# GMSL_DESERIALIZER.net
KiCad netlist of a schematic drawn in Altium Designer
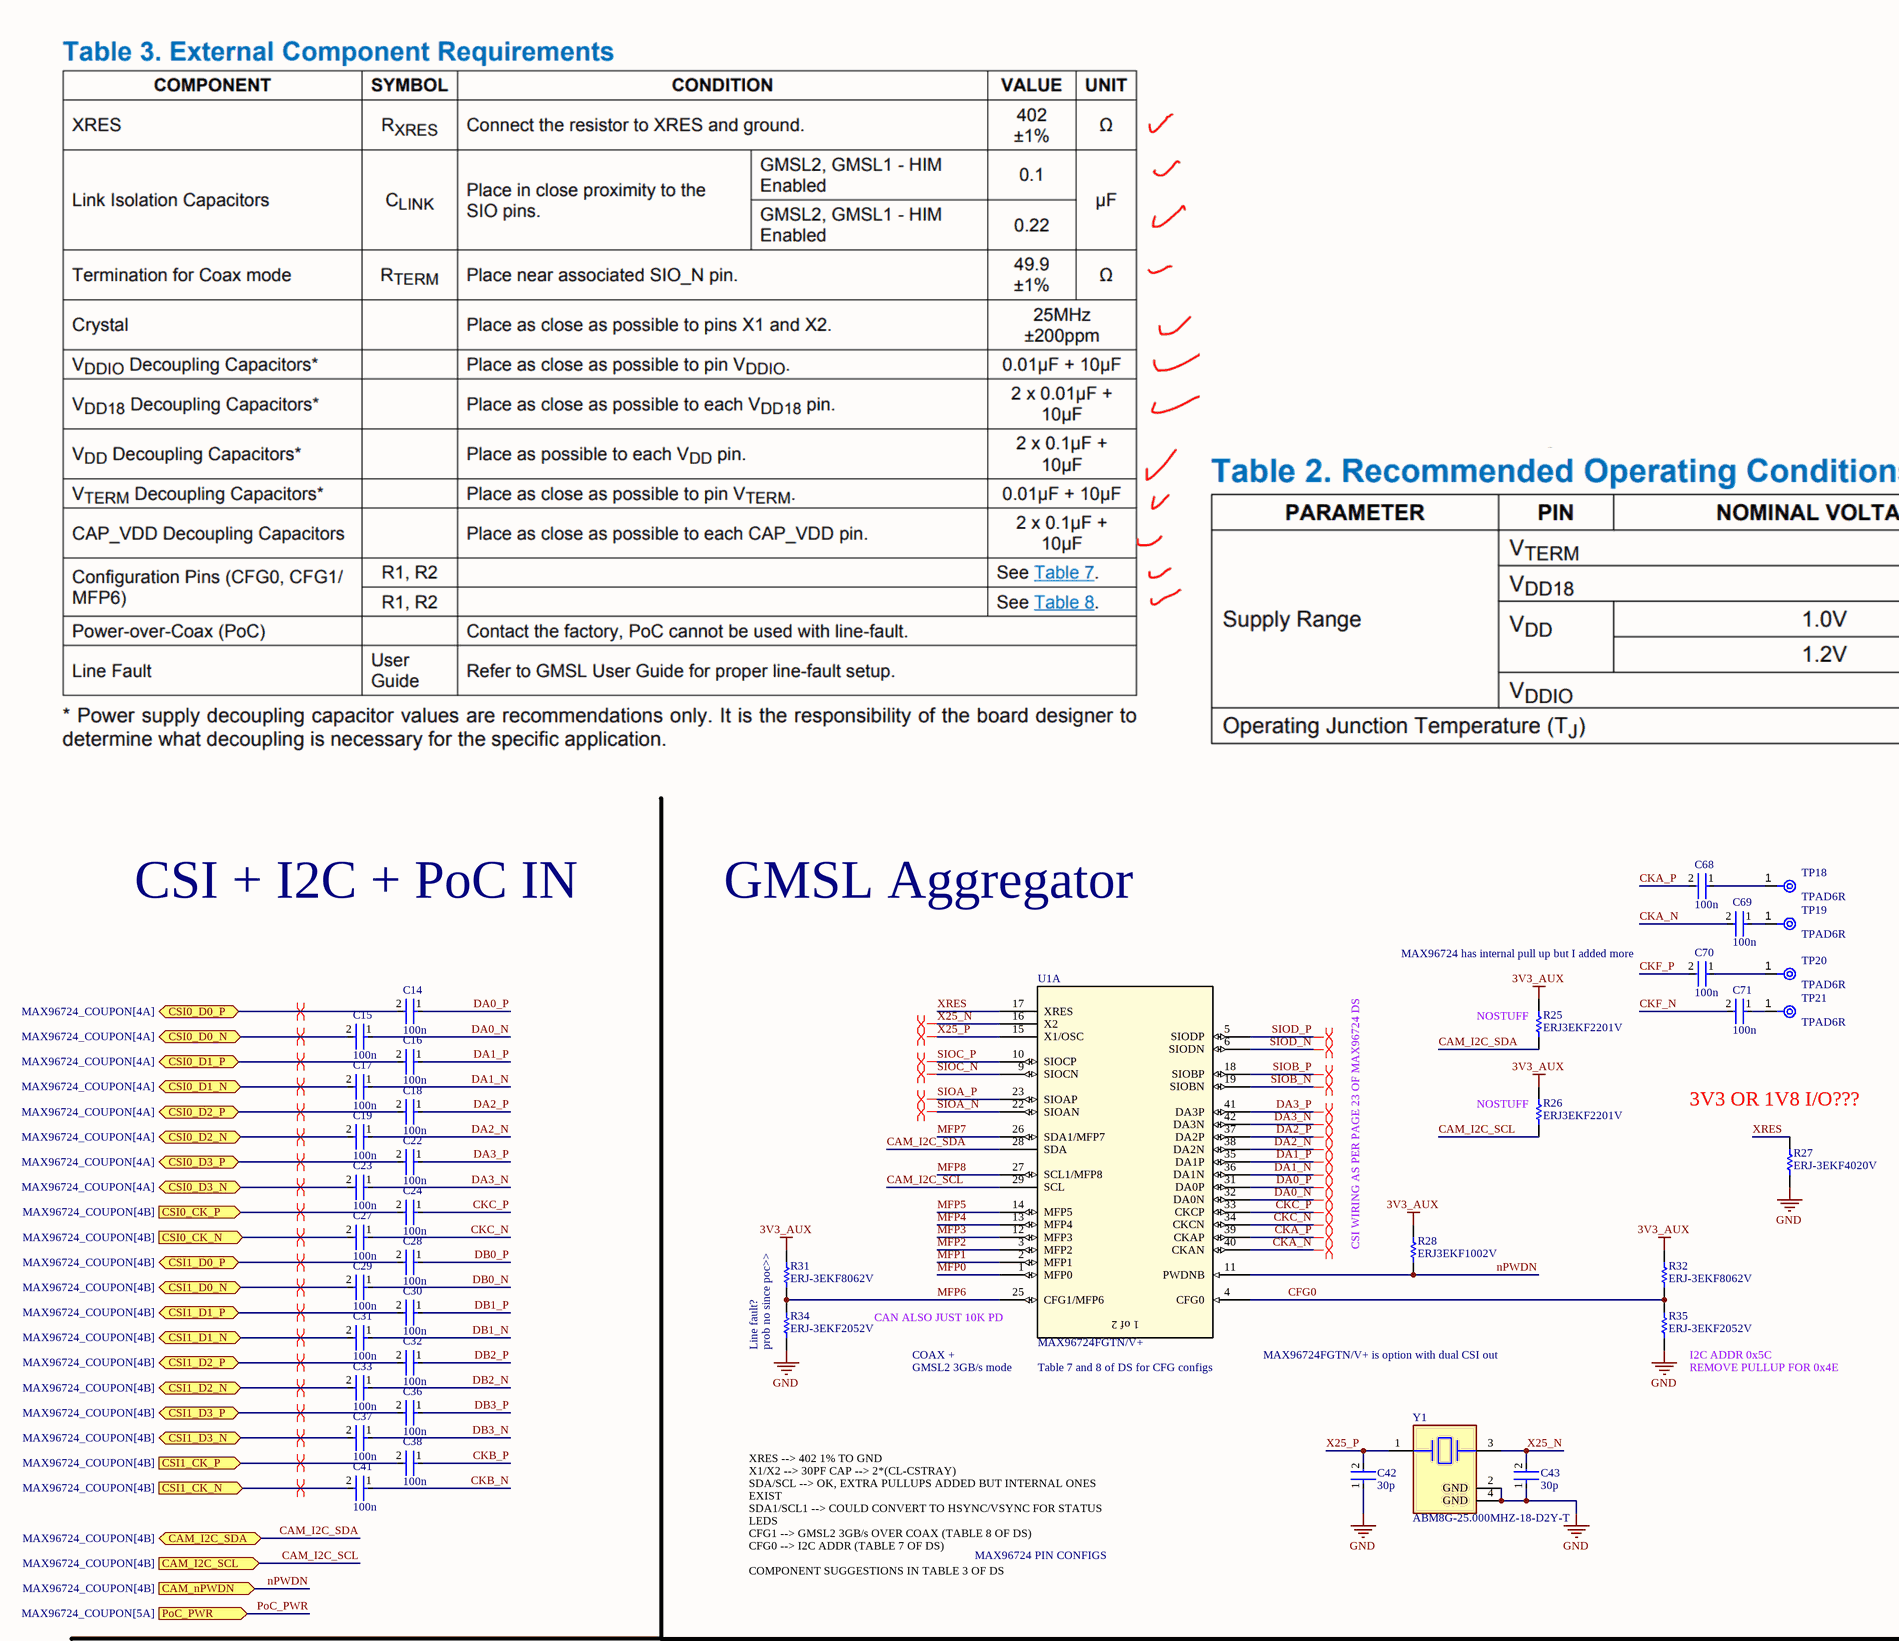
[diagram p0: GMSL_DESERIALIZER.SchDoc, top left]
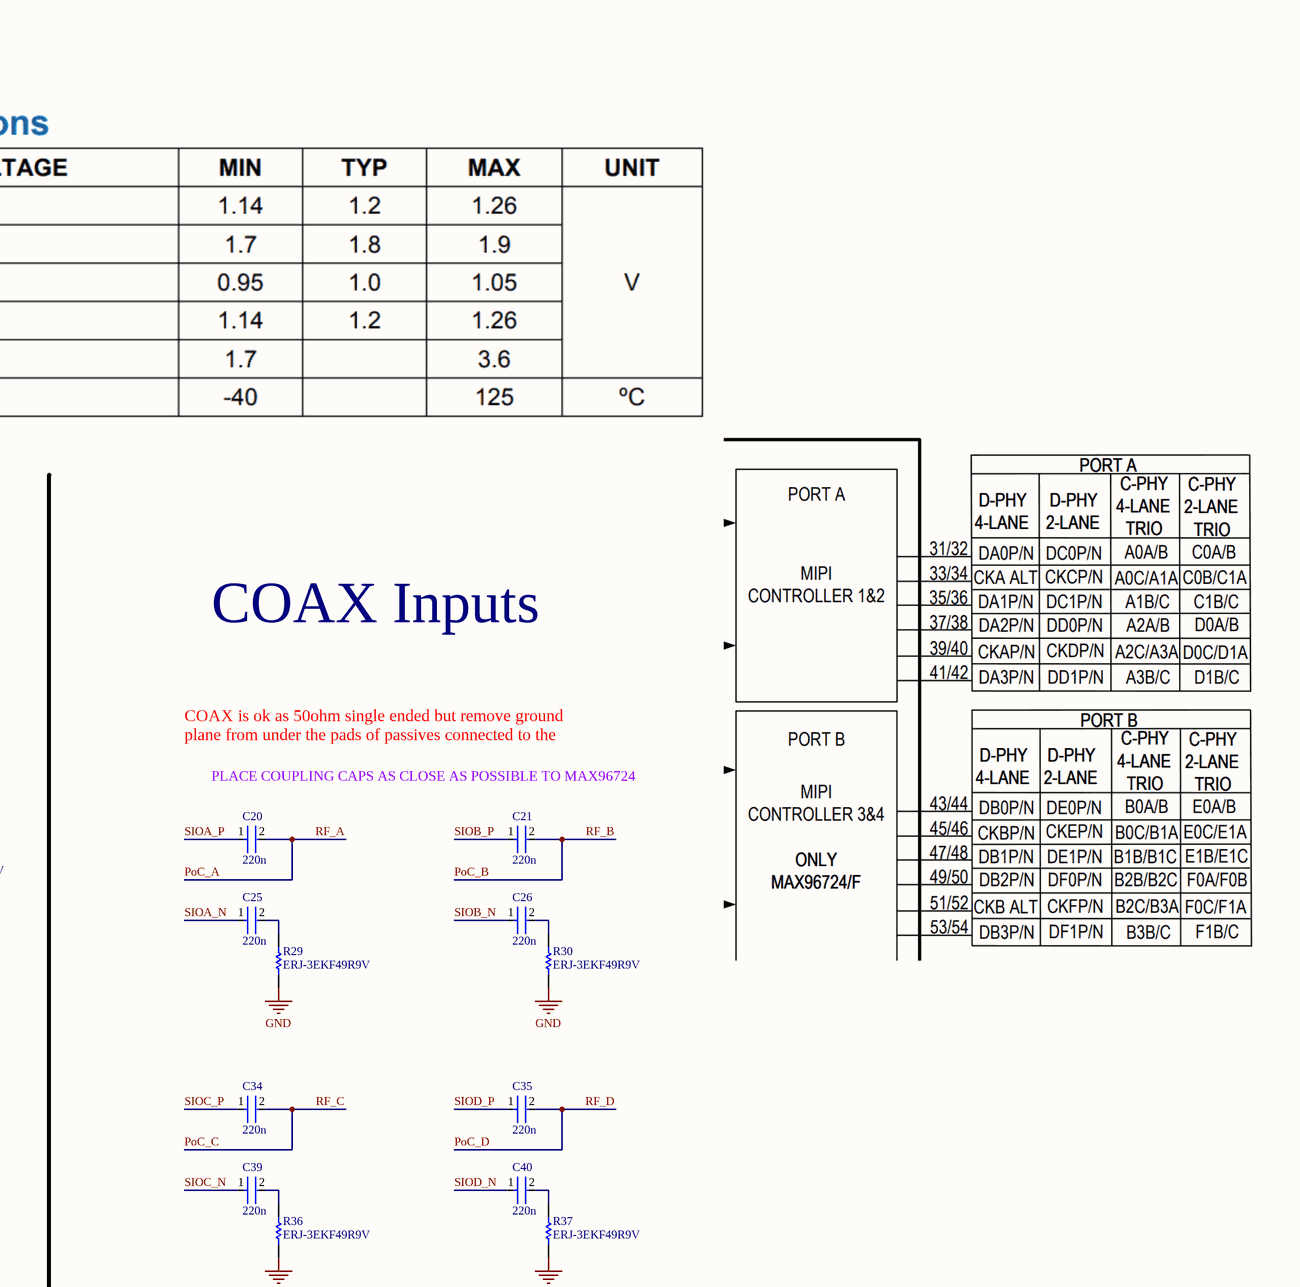
[diagram p1: GMSL_DESERIALIZER.SchDoc, top right]
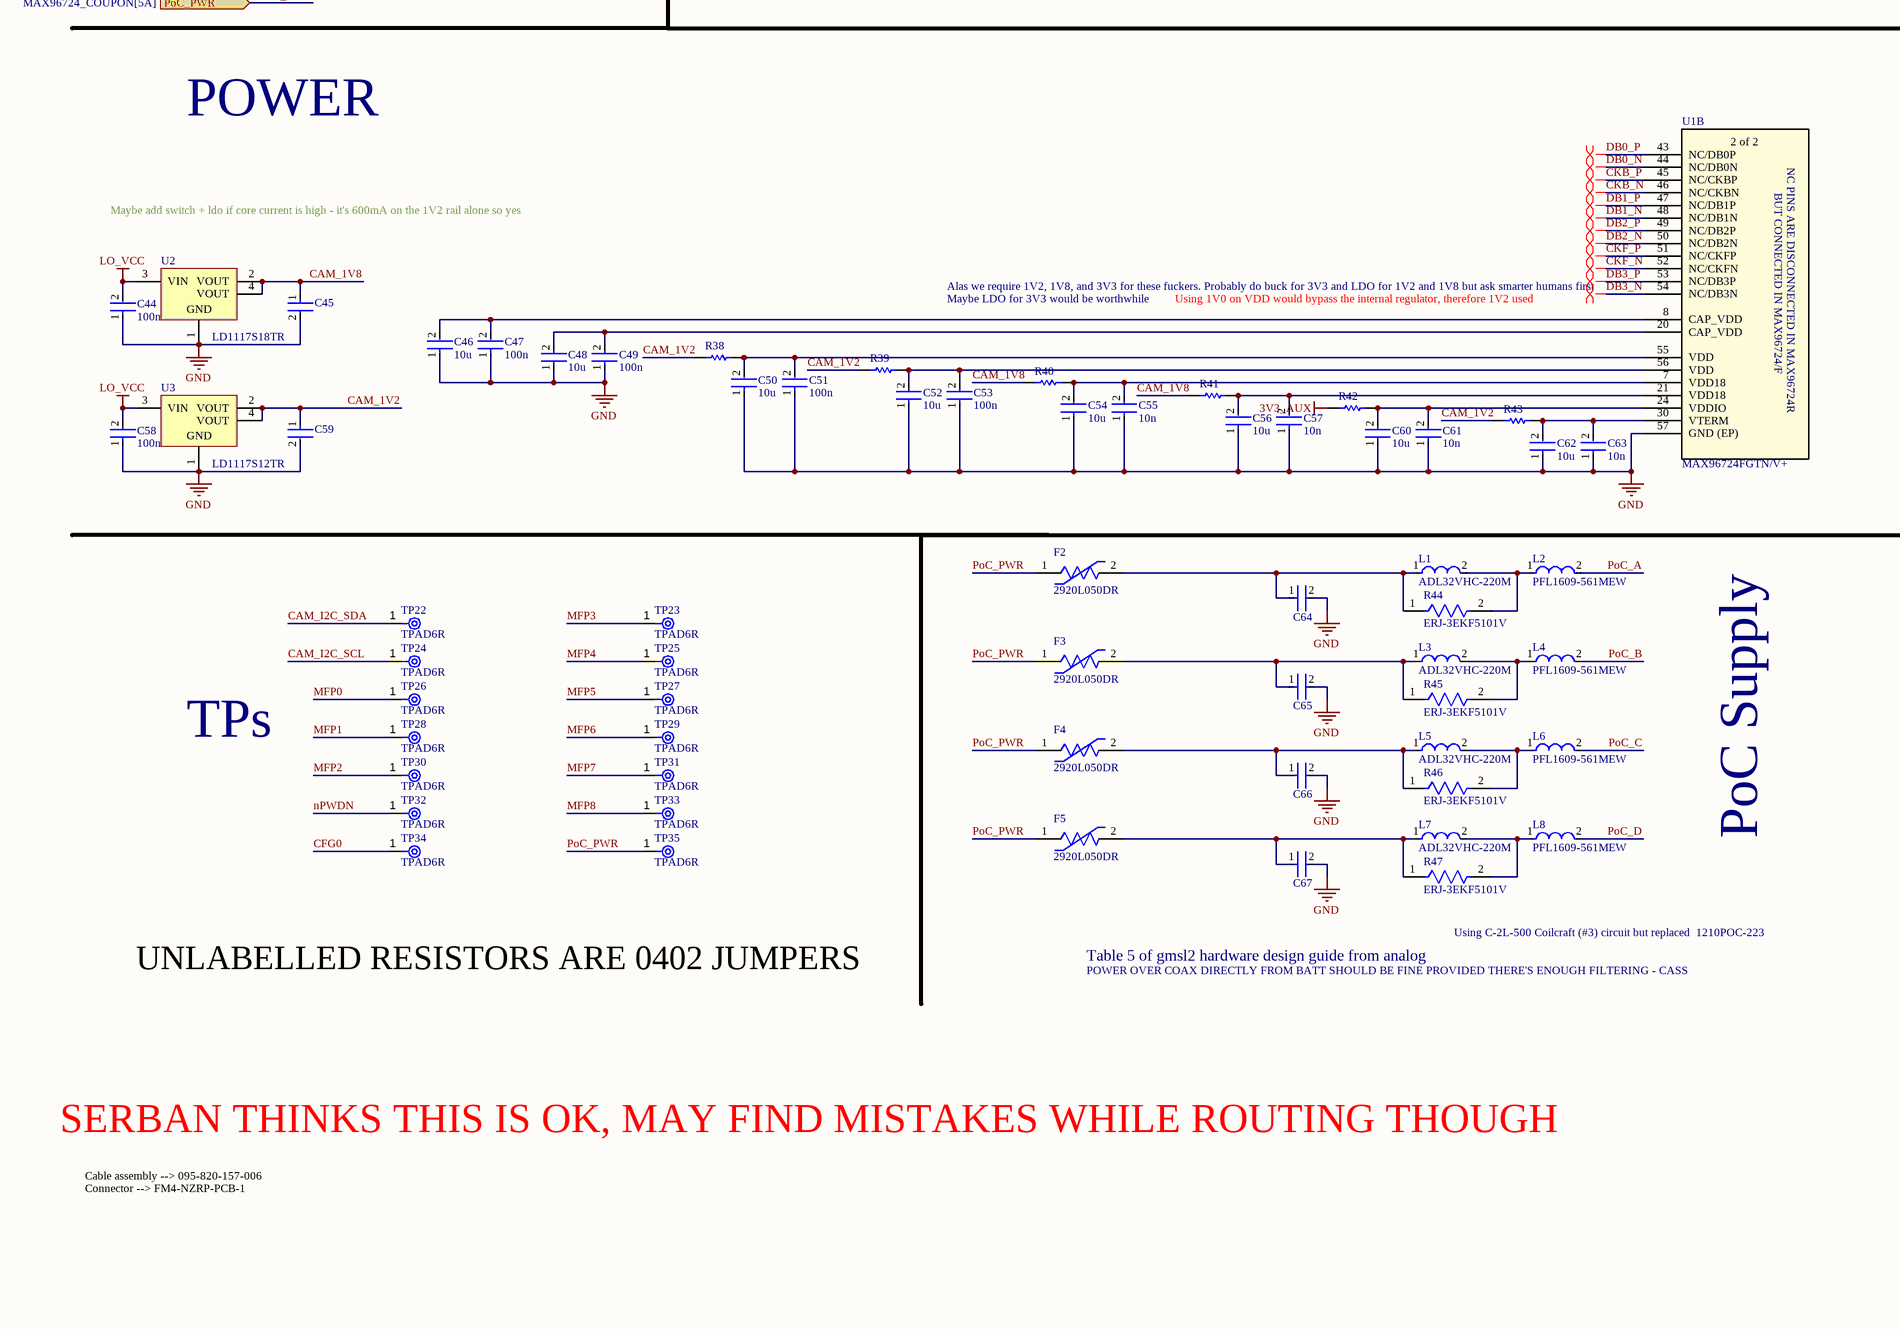
[diagram p2: GMSL_DESERIALIZER.SchDoc, bottom left]
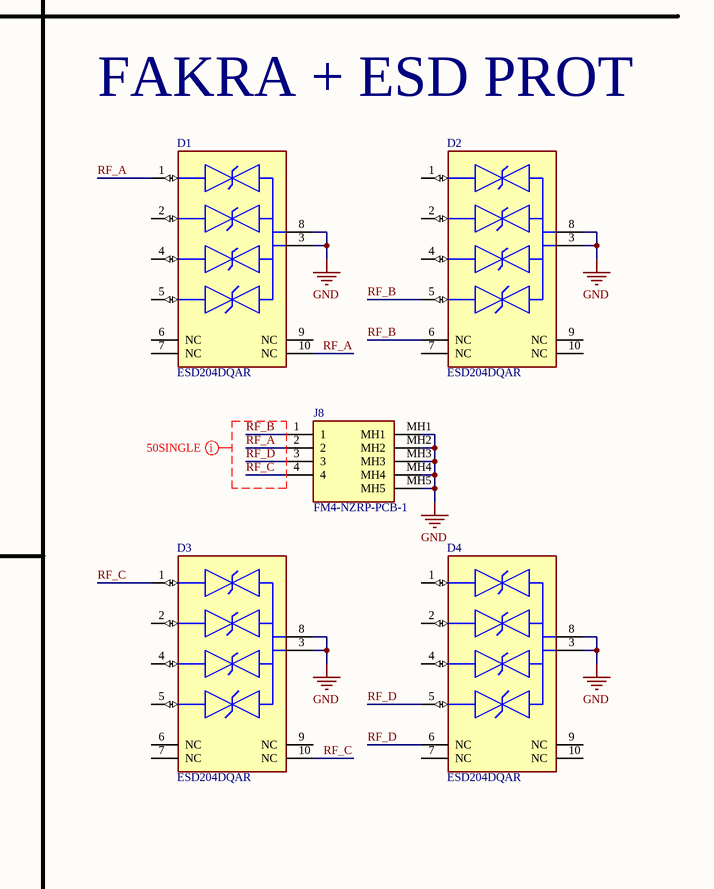
[diagram p3: GMSL_DESERIALIZER.SchDoc, bottom right]

(export (version "E")
  (design (tool "Eeschema 10.0.6"))
  (components
    (comp (ref "C14")
      (value "100n")
      (footprint "FP-0402-L_1_0_0_05-W_0_5-IPC_A")
      (description "LARGE PADS, 0402 CAP, CHANGE COMMENT TO MATCH REAL P/N")
      (libsource (lib "Space Concordia") (part "b4654b650e69147ec39a6b967a45e02"))
    )
    (comp (ref "C15")
      (value "100n")
      (footprint "FP-0402-L_1_0_0_05-W_0_5-IPC_A")
      (description "LARGE PADS, 0402 CAP, CHANGE COMMENT TO MATCH REAL P/N")
      (libsource (lib "Space Concordia") (part "b4654b650e69147ec39a6b967a45e02"))
    )
    (comp (ref "C16")
      (value "100n")
      (footprint "FP-0402-L_1_0_0_05-W_0_5-IPC_A")
      (description "LARGE PADS, 0402 CAP, CHANGE COMMENT TO MATCH REAL P/N")
      (libsource (lib "Space Concordia") (part "b4654b650e69147ec39a6b967a45e02"))
    )
    (comp (ref "C17")
      (value "100n")
      (footprint "FP-0402-L_1_0_0_05-W_0_5-IPC_A")
      (description "LARGE PADS, 0402 CAP, CHANGE COMMENT TO MATCH REAL P/N")
      (libsource (lib "Space Concordia") (part "b4654b650e69147ec39a6b967a45e02"))
    )
    (comp (ref "C18")
      (value "100n")
      (footprint "FP-0402-L_1_0_0_05-W_0_5-IPC_A")
      (description "LARGE PADS, 0402 CAP, CHANGE COMMENT TO MATCH REAL P/N")
      (libsource (lib "Space Concordia") (part "b4654b650e69147ec39a6b967a45e02"))
    )
    (comp (ref "C19")
      (value "100n")
      (footprint "FP-0402-L_1_0_0_05-W_0_5-IPC_A")
      (description "LARGE PADS, 0402 CAP, CHANGE COMMENT TO MATCH REAL P/N")
      (libsource (lib "Space Concordia") (part "b4654b650e69147ec39a6b967a45e02"))
    )
    (comp (ref "C20")
      (value "220n")
      (footprint "FP-0402-L_1_0_0_05-W_0_5-IPC_A")
      (description "LARGE PADS, 0402 CAP, CHANGE COMMENT TO MATCH REAL P/N")
      (libsource (lib "Space Concordia") (part "b4654b650e69147ec39a6b967a45e02"))
    )
    (comp (ref "C21")
      (value "220n")
      (footprint "FP-0402-L_1_0_0_05-W_0_5-IPC_A")
      (description "LARGE PADS, 0402 CAP, CHANGE COMMENT TO MATCH REAL P/N")
      (libsource (lib "Space Concordia") (part "b4654b650e69147ec39a6b967a45e02"))
    )
    (comp (ref "C22")
      (value "100n")
      (footprint "FP-0402-L_1_0_0_05-W_0_5-IPC_A")
      (description "LARGE PADS, 0402 CAP, CHANGE COMMENT TO MATCH REAL P/N")
      (libsource (lib "Space Concordia") (part "b4654b650e69147ec39a6b967a45e02"))
    )
    (comp (ref "C23")
      (value "100n")
      (footprint "FP-0402-L_1_0_0_05-W_0_5-IPC_A")
      (description "LARGE PADS, 0402 CAP, CHANGE COMMENT TO MATCH REAL P/N")
      (libsource (lib "Space Concordia") (part "b4654b650e69147ec39a6b967a45e02"))
    )
    (comp (ref "C24")
      (value "100n")
      (footprint "FP-0402-L_1_0_0_05-W_0_5-IPC_A")
      (description "LARGE PADS, 0402 CAP, CHANGE COMMENT TO MATCH REAL P/N")
      (libsource (lib "Space Concordia") (part "b4654b650e69147ec39a6b967a45e02"))
    )
    (comp (ref "C25")
      (value "220n")
      (footprint "FP-0402-L_1_0_0_05-W_0_5-IPC_A")
      (description "LARGE PADS, 0402 CAP, CHANGE COMMENT TO MATCH REAL P/N")
      (libsource (lib "Space Concordia") (part "b4654b650e69147ec39a6b967a45e02"))
    )
    (comp (ref "C26")
      (value "220n")
      (footprint "FP-0402-L_1_0_0_05-W_0_5-IPC_A")
      (description "LARGE PADS, 0402 CAP, CHANGE COMMENT TO MATCH REAL P/N")
      (libsource (lib "Space Concordia") (part "b4654b650e69147ec39a6b967a45e02"))
    )
    (comp (ref "C27")
      (value "100n")
      (footprint "FP-0402-L_1_0_0_05-W_0_5-IPC_A")
      (description "LARGE PADS, 0402 CAP, CHANGE COMMENT TO MATCH REAL P/N")
      (libsource (lib "Space Concordia") (part "b4654b650e69147ec39a6b967a45e02"))
    )
    (comp (ref "C28")
      (value "100n")
      (footprint "FP-0402-L_1_0_0_05-W_0_5-IPC_A")
      (description "LARGE PADS, 0402 CAP, CHANGE COMMENT TO MATCH REAL P/N")
      (libsource (lib "Space Concordia") (part "b4654b650e69147ec39a6b967a45e02"))
    )
    (comp (ref "C29")
      (value "100n")
      (footprint "FP-0402-L_1_0_0_05-W_0_5-IPC_A")
      (description "LARGE PADS, 0402 CAP, CHANGE COMMENT TO MATCH REAL P/N")
      (libsource (lib "Space Concordia") (part "b4654b650e69147ec39a6b967a45e02"))
    )
    (comp (ref "C30")
      (value "100n")
      (footprint "FP-0402-L_1_0_0_05-W_0_5-IPC_A")
      (description "LARGE PADS, 0402 CAP, CHANGE COMMENT TO MATCH REAL P/N")
      (libsource (lib "Space Concordia") (part "b4654b650e69147ec39a6b967a45e02"))
    )
    (comp (ref "C31")
      (value "100n")
      (footprint "FP-0402-L_1_0_0_05-W_0_5-IPC_A")
      (description "LARGE PADS, 0402 CAP, CHANGE COMMENT TO MATCH REAL P/N")
      (libsource (lib "Space Concordia") (part "b4654b650e69147ec39a6b967a45e02"))
    )
    (comp (ref "C32")
      (value "100n")
      (footprint "FP-0402-L_1_0_0_05-W_0_5-IPC_A")
      (description "LARGE PADS, 0402 CAP, CHANGE COMMENT TO MATCH REAL P/N")
      (libsource (lib "Space Concordia") (part "b4654b650e69147ec39a6b967a45e02"))
    )
    (comp (ref "C33")
      (value "100n")
      (footprint "FP-0402-L_1_0_0_05-W_0_5-IPC_A")
      (description "LARGE PADS, 0402 CAP, CHANGE COMMENT TO MATCH REAL P/N")
      (libsource (lib "Space Concordia") (part "b4654b650e69147ec39a6b967a45e02"))
    )
    (comp (ref "C34")
      (value "220n")
      (footprint "FP-0402-L_1_0_0_05-W_0_5-IPC_A")
      (description "LARGE PADS, 0402 CAP, CHANGE COMMENT TO MATCH REAL P/N")
      (libsource (lib "Space Concordia") (part "b4654b650e69147ec39a6b967a45e02"))
    )
    (comp (ref "C35")
      (value "220n")
      (footprint "FP-0402-L_1_0_0_05-W_0_5-IPC_A")
      (description "LARGE PADS, 0402 CAP, CHANGE COMMENT TO MATCH REAL P/N")
      (libsource (lib "Space Concordia") (part "b4654b650e69147ec39a6b967a45e02"))
    )
    (comp (ref "C36")
      (value "100n")
      (footprint "FP-0402-L_1_0_0_05-W_0_5-IPC_A")
      (description "LARGE PADS, 0402 CAP, CHANGE COMMENT TO MATCH REAL P/N")
      (libsource (lib "Space Concordia") (part "b4654b650e69147ec39a6b967a45e02"))
    )
    (comp (ref "C37")
      (value "100n")
      (footprint "FP-0402-L_1_0_0_05-W_0_5-IPC_A")
      (description "LARGE PADS, 0402 CAP, CHANGE COMMENT TO MATCH REAL P/N")
      (libsource (lib "Space Concordia") (part "b4654b650e69147ec39a6b967a45e02"))
    )
    (comp (ref "C38")
      (value "100n")
      (footprint "FP-0402-L_1_0_0_05-W_0_5-IPC_A")
      (description "LARGE PADS, 0402 CAP, CHANGE COMMENT TO MATCH REAL P/N")
      (libsource (lib "Space Concordia") (part "b4654b650e69147ec39a6b967a45e02"))
    )
    (comp (ref "C39")
      (value "220n")
      (footprint "FP-0402-L_1_0_0_05-W_0_5-IPC_A")
      (description "LARGE PADS, 0402 CAP, CHANGE COMMENT TO MATCH REAL P/N")
      (libsource (lib "Space Concordia") (part "b4654b650e69147ec39a6b967a45e02"))
    )
    (comp (ref "C40")
      (value "220n")
      (footprint "FP-0402-L_1_0_0_05-W_0_5-IPC_A")
      (description "LARGE PADS, 0402 CAP, CHANGE COMMENT TO MATCH REAL P/N")
      (libsource (lib "Space Concordia") (part "b4654b650e69147ec39a6b967a45e02"))
    )
    (comp (ref "C41")
      (value "100n")
      (footprint "FP-0402-L_1_0_0_05-W_0_5-IPC_A")
      (description "LARGE PADS, 0402 CAP, CHANGE COMMENT TO MATCH REAL P/N")
      (libsource (lib "Space Concordia") (part "b4654b650e69147ec39a6b967a45e02"))
    )
    (comp (ref "C42")
      (value "30p")
      (footprint "FP-0402-L_1_0_0_05-W_0_5-IPC_A")
      (description "LARGE PADS, 0402 CAP, CHANGE COMMENT TO MATCH REAL P/N")
      (libsource (lib "Space Concordia") (part "b4654b650e69147ec39a6b967a45e02"))
    )
    (comp (ref "C43")
      (value "30p")
      (footprint "FP-0402-L_1_0_0_05-W_0_5-IPC_A")
      (description "LARGE PADS, 0402 CAP, CHANGE COMMENT TO MATCH REAL P/N")
      (libsource (lib "Space Concordia") (part "b4654b650e69147ec39a6b967a45e02"))
    )
    (comp (ref "C44")
      (value "100n")
      (footprint "FP-0402-L_1_0_0_05-W_0_5-IPC_A")
      (description "LARGE PADS, 0402 CAP, CHANGE COMMENT TO MATCH REAL P/N")
      (libsource (lib "Space Concordia") (part "b4654b650e69147ec39a6b967a45e02"))
    )
    (comp (ref "C45")
      (value "GRM188R60J106ME47D")
      (footprint "FP-GRM188-0_1-e0_2_0_55-IPC_A")
      (description "Chip Multilayer Ceramic Capacitors for General Purpose, 0603, 10uF, X5R, 15%, 20%, 6.3V")
      (fields (field (name "VOLTAGE") "6.3V") (field (name "TOLERANCE") "20%"))
      (libsource (lib "Altium Content Vault") (part "02cd4be3c70576c341d710602a673aa"))
    )
    (comp (ref "C46")
      (value "10u")
      (footprint "FP-0402-L_1_0_0_05-W_0_5-IPC_A")
      (description "LARGE PADS, 0402 CAP, CHANGE COMMENT TO MATCH REAL P/N")
      (libsource (lib "Space Concordia") (part "b4654b650e69147ec39a6b967a45e02"))
    )
    (comp (ref "C47")
      (value "100n")
      (footprint "FP-0402-L_1_0_0_05-W_0_5-IPC_A")
      (description "LARGE PADS, 0402 CAP, CHANGE COMMENT TO MATCH REAL P/N")
      (libsource (lib "Space Concordia") (part "b4654b650e69147ec39a6b967a45e02"))
    )
    (comp (ref "C48")
      (value "10u")
      (footprint "FP-0402-L_1_0_0_05-W_0_5-IPC_A")
      (description "LARGE PADS, 0402 CAP, CHANGE COMMENT TO MATCH REAL P/N")
      (libsource (lib "Space Concordia") (part "b4654b650e69147ec39a6b967a45e02"))
    )
    (comp (ref "C49")
      (value "100n")
      (footprint "FP-0402-L_1_0_0_05-W_0_5-IPC_A")
      (description "LARGE PADS, 0402 CAP, CHANGE COMMENT TO MATCH REAL P/N")
      (libsource (lib "Space Concordia") (part "b4654b650e69147ec39a6b967a45e02"))
    )
    (comp (ref "C50")
      (value "10u")
      (footprint "FP-0402-L_1_0_0_05-W_0_5-IPC_A")
      (description "LARGE PADS, 0402 CAP, CHANGE COMMENT TO MATCH REAL P/N")
      (libsource (lib "Space Concordia") (part "b4654b650e69147ec39a6b967a45e02"))
    )
    (comp (ref "C51")
      (value "100n")
      (footprint "FP-0402-L_1_0_0_05-W_0_5-IPC_A")
      (description "LARGE PADS, 0402 CAP, CHANGE COMMENT TO MATCH REAL P/N")
      (libsource (lib "Space Concordia") (part "b4654b650e69147ec39a6b967a45e02"))
    )
    (comp (ref "C52")
      (value "10u")
      (footprint "FP-0402-L_1_0_0_05-W_0_5-IPC_A")
      (description "LARGE PADS, 0402 CAP, CHANGE COMMENT TO MATCH REAL P/N")
      (libsource (lib "Space Concordia") (part "b4654b650e69147ec39a6b967a45e02"))
    )
    (comp (ref "C53")
      (value "100n")
      (footprint "FP-0402-L_1_0_0_05-W_0_5-IPC_A")
      (description "LARGE PADS, 0402 CAP, CHANGE COMMENT TO MATCH REAL P/N")
      (libsource (lib "Space Concordia") (part "b4654b650e69147ec39a6b967a45e02"))
    )
    (comp (ref "C54")
      (value "10u")
      (footprint "FP-0402-L_1_0_0_05-W_0_5-IPC_A")
      (description "LARGE PADS, 0402 CAP, CHANGE COMMENT TO MATCH REAL P/N")
      (libsource (lib "Space Concordia") (part "b4654b650e69147ec39a6b967a45e02"))
    )
    (comp (ref "C55")
      (value "10n")
      (footprint "FP-0402-L_1_0_0_05-W_0_5-IPC_A")
      (description "LARGE PADS, 0402 CAP, CHANGE COMMENT TO MATCH REAL P/N")
      (libsource (lib "Space Concordia") (part "b4654b650e69147ec39a6b967a45e02"))
    )
    (comp (ref "C56")
      (value "10u")
      (footprint "FP-0402-L_1_0_0_05-W_0_5-IPC_A")
      (description "LARGE PADS, 0402 CAP, CHANGE COMMENT TO MATCH REAL P/N")
      (libsource (lib "Space Concordia") (part "b4654b650e69147ec39a6b967a45e02"))
    )
    (comp (ref "C57")
      (value "10n")
      (footprint "FP-0402-L_1_0_0_05-W_0_5-IPC_A")
      (description "LARGE PADS, 0402 CAP, CHANGE COMMENT TO MATCH REAL P/N")
      (libsource (lib "Space Concordia") (part "b4654b650e69147ec39a6b967a45e02"))
    )
    (comp (ref "C58")
      (value "100n")
      (footprint "FP-0402-L_1_0_0_05-W_0_5-IPC_A")
      (description "LARGE PADS, 0402 CAP, CHANGE COMMENT TO MATCH REAL P/N")
      (libsource (lib "Space Concordia") (part "b4654b650e69147ec39a6b967a45e02"))
    )
    (comp (ref "C59")
      (value "GRM188R60J106ME47D")
      (footprint "FP-GRM188-0_1-e0_2_0_55-IPC_A")
      (description "Chip Multilayer Ceramic Capacitors for General Purpose, 0603, 10uF, X5R, 15%, 20%, 6.3V")
      (fields (field (name "VOLTAGE") "6.3V") (field (name "TOLERANCE") "20%"))
      (libsource (lib "Altium Content Vault") (part "02cd4be3c70576c341d710602a673aa"))
    )
    (comp (ref "C60")
      (value "10u")
      (footprint "FP-0402-L_1_0_0_05-W_0_5-IPC_A")
      (description "LARGE PADS, 0402 CAP, CHANGE COMMENT TO MATCH REAL P/N")
      (libsource (lib "Space Concordia") (part "b4654b650e69147ec39a6b967a45e02"))
    )
    (comp (ref "C61")
      (value "10n")
      (footprint "FP-0402-L_1_0_0_05-W_0_5-IPC_A")
      (description "LARGE PADS, 0402 CAP, CHANGE COMMENT TO MATCH REAL P/N")
      (libsource (lib "Space Concordia") (part "b4654b650e69147ec39a6b967a45e02"))
    )
    (comp (ref "C62")
      (value "10u")
      (footprint "FP-0402-L_1_0_0_05-W_0_5-IPC_A")
      (description "LARGE PADS, 0402 CAP, CHANGE COMMENT TO MATCH REAL P/N")
      (libsource (lib "Space Concordia") (part "b4654b650e69147ec39a6b967a45e02"))
    )
    (comp (ref "C63")
      (value "10n")
      (footprint "FP-0402-L_1_0_0_05-W_0_5-IPC_A")
      (description "LARGE PADS, 0402 CAP, CHANGE COMMENT TO MATCH REAL P/N")
      (libsource (lib "Space Concordia") (part "b4654b650e69147ec39a6b967a45e02"))
    )
    (comp (ref "C64")
      (value "GRM21BR61E226ME44L")
      (footprint "FP-GRM21B-0_2-e0_2_0_7-IPC_B")
      (description "Chip Multilayer Ceramic Capacitors for General Purpose, 0805, 22uF, X5R, 15%, 20%, 25V")
      (fields (field (name "TOLERANCE") "20%") (field (name "VOLTAGE") "25V"))
      (libsource (lib "Altium Content Vault") (part "b4654b650e69147ec39a6b967a45e02"))
    )
    (comp (ref "C65")
      (value "GRM21BR61E226ME44L")
      (footprint "FP-GRM21B-0_2-e0_2_0_7-IPC_B")
      (description "Chip Multilayer Ceramic Capacitors for General Purpose, 0805, 22uF, X5R, 15%, 20%, 25V")
      (fields (field (name "TOLERANCE") "20%") (field (name "VOLTAGE") "25V"))
      (libsource (lib "Altium Content Vault") (part "b4654b650e69147ec39a6b967a45e02"))
    )
    (comp (ref "C66")
      (value "GRM21BR61E226ME44L")
      (footprint "FP-GRM21B-0_2-e0_2_0_7-IPC_B")
      (description "Chip Multilayer Ceramic Capacitors for General Purpose, 0805, 22uF, X5R, 15%, 20%, 25V")
      (fields (field (name "TOLERANCE") "20%") (field (name "VOLTAGE") "25V"))
      (libsource (lib "Altium Content Vault") (part "b4654b650e69147ec39a6b967a45e02"))
    )
    (comp (ref "C67")
      (value "GRM21BR61E226ME44L")
      (footprint "FP-GRM21B-0_2-e0_2_0_7-IPC_B")
      (description "Chip Multilayer Ceramic Capacitors for General Purpose, 0805, 22uF, X5R, 15%, 20%, 25V")
      (fields (field (name "TOLERANCE") "20%") (field (name "VOLTAGE") "25V"))
      (libsource (lib "Altium Content Vault") (part "b4654b650e69147ec39a6b967a45e02"))
    )
    (comp (ref "C68")
      (value "100n")
      (footprint "FP-0402-L_1_0_0_05-W_0_5-IPC_A")
      (description "LARGE PADS, 0402 CAP, CHANGE COMMENT TO MATCH REAL P/N")
      (libsource (lib "Space Concordia") (part "b4654b650e69147ec39a6b967a45e02"))
    )
    (comp (ref "C69")
      (value "100n")
      (footprint "FP-0402-L_1_0_0_05-W_0_5-IPC_A")
      (description "LARGE PADS, 0402 CAP, CHANGE COMMENT TO MATCH REAL P/N")
      (libsource (lib "Space Concordia") (part "b4654b650e69147ec39a6b967a45e02"))
    )
    (comp (ref "C70")
      (value "100n")
      (footprint "FP-0402-L_1_0_0_05-W_0_5-IPC_A")
      (description "LARGE PADS, 0402 CAP, CHANGE COMMENT TO MATCH REAL P/N")
      (libsource (lib "Space Concordia") (part "b4654b650e69147ec39a6b967a45e02"))
    )
    (comp (ref "C71")
      (value "100n")
      (footprint "FP-0402-L_1_0_0_05-W_0_5-IPC_A")
      (description "LARGE PADS, 0402 CAP, CHANGE COMMENT TO MATCH REAL P/N")
      (libsource (lib "Space Concordia") (part "b4654b650e69147ec39a6b967a45e02"))
    )
    (comp (ref "D1")
      (value "ESD204DQAR")
      (footprint "FP-DQA0010A-MFG")
      (description "4-CHANNEL LOW-CAPACITANCE SURGE")
      (fields
        (field (name "MANUFACTURER") "Texas Instruments")
        (field (name "OCTOPART") "https://octopart.com/esd204dqar-texas+instruments-89917476")
      )
      (libsource (lib "Altium Content Vault") (part "1465e58c1818c7767b55926832f0bf5"))
    )
    (comp (ref "D2")
      (value "ESD204DQAR")
      (footprint "FP-DQA0010A-MFG")
      (description "4-CHANNEL LOW-CAPACITANCE SURGE")
      (fields
        (field (name "MANUFACTURER") "Texas Instruments")
        (field (name "OCTOPART") "https://octopart.com/esd204dqar-texas+instruments-89917476")
      )
      (libsource (lib "Altium Content Vault") (part "1465e58c1818c7767b55926832f0bf5"))
    )
    (comp (ref "D3")
      (value "ESD204DQAR")
      (footprint "FP-DQA0010A-MFG")
      (description "4-CHANNEL LOW-CAPACITANCE SURGE")
      (fields
        (field (name "MANUFACTURER") "Texas Instruments")
        (field (name "OCTOPART") "https://octopart.com/esd204dqar-texas+instruments-89917476")
      )
      (libsource (lib "Altium Content Vault") (part "1465e58c1818c7767b55926832f0bf5"))
    )
    (comp (ref "D4")
      (value "ESD204DQAR")
      (footprint "FP-DQA0010A-MFG")
      (description "4-CHANNEL LOW-CAPACITANCE SURGE")
      (fields
        (field (name "MANUFACTURER") "Texas Instruments")
        (field (name "OCTOPART") "https://octopart.com/esd204dqar-texas+instruments-89917476")
      )
      (libsource (lib "Altium Content Vault") (part "1465e58c1818c7767b55926832f0bf5"))
    )
    (comp (ref "F2")
      (value "2920L050DR")
      (footprint "FP-2920L050DR-MFG")
      (description "PTC RESET FUSE 60V 500MA 2920")
      (libsource (lib "Altium Content Vault") (part "1c6d77a0208143737455a0c7eb396be"))
    )
    (comp (ref "F3")
      (value "2920L050DR")
      (footprint "FP-2920L050DR-MFG")
      (description "PTC RESET FUSE 60V 500MA 2920")
      (libsource (lib "Altium Content Vault") (part "1c6d77a0208143737455a0c7eb396be"))
    )
    (comp (ref "F4")
      (value "2920L050DR")
      (footprint "FP-2920L050DR-MFG")
      (description "PTC RESET FUSE 60V 500MA 2920")
      (libsource (lib "Altium Content Vault") (part "1c6d77a0208143737455a0c7eb396be"))
    )
    (comp (ref "F5")
      (value "2920L050DR")
      (footprint "FP-2920L050DR-MFG")
      (description "PTC RESET FUSE 60V 500MA 2920")
      (libsource (lib "Altium Content Vault") (part "1c6d77a0208143737455a0c7eb396be"))
    )
    (comp (ref "J8")
      (value "FM4-NZRP-PCB-1")
      (footprint "FM4-NZRP-PCB-1-Footprint-1")
      (description "Connector RF Mini-FAKRA Plug 9GHz 50Ohm Solder Right Angle Through Hole")
      (libsource (lib "Space Concordia") (part "CMP-002-00085-1"))
    )
    (comp (ref "L1")
      (value "ADL32VHC-220M")
      (footprint "FP-1210POC-MFG")
      (description "NOT COILCRAFT - ACTUAL P# --> ADL32VHC-220M\r\n - Power Injection Chokes for PoC")
      (fields
        (field (name "MANUFACTURER") "coilcraft")
        (field (name "OCTOPART") "https://octopart.com/1210poc-223mrc-coilcraft-103207315")
      )
      (libsource (lib "Altium Content Vault") (part "725321dda6339637d4d059423bc1c3c"))
    )
    (comp (ref "L2")
      (value "PFL1609-561MEW")
      (footprint "FP-PFL1609-MFG")
      (description "Fixed Inductors PFL1609 Low Profile 0.56 uH 20 % 1.4 A")
      (fields (field (name "MANUFACTURER") "coilcraft") (field (name "TOLERANCE") "20%"))
      (libsource (lib "Altium Content Vault") (part "725321dda6339637d4d059423bc1c3c"))
    )
    (comp (ref "L3")
      (value "ADL32VHC-220M")
      (footprint "FP-1210POC-MFG")
      (description "NOT COILCRAFT - ACTUAL P# --> ADL32VHC-220M\r\n - Power Injection Chokes for PoC")
      (fields
        (field (name "MANUFACTURER") "coilcraft")
        (field (name "OCTOPART") "https://octopart.com/1210poc-223mrc-coilcraft-103207315")
      )
      (libsource (lib "Altium Content Vault") (part "725321dda6339637d4d059423bc1c3c"))
    )
    (comp (ref "L4")
      (value "PFL1609-561MEW")
      (footprint "FP-PFL1609-MFG")
      (description "Fixed Inductors PFL1609 Low Profile 0.56 uH 20 % 1.4 A")
      (fields (field (name "MANUFACTURER") "coilcraft") (field (name "TOLERANCE") "20%"))
      (libsource (lib "Altium Content Vault") (part "725321dda6339637d4d059423bc1c3c"))
    )
    (comp (ref "L5")
      (value "ADL32VHC-220M")
      (footprint "FP-1210POC-MFG")
      (description "NOT COILCRAFT - ACTUAL P# --> ADL32VHC-220M\r\n - Power Injection Chokes for PoC")
      (fields
        (field (name "MANUFACTURER") "coilcraft")
        (field (name "OCTOPART") "https://octopart.com/1210poc-223mrc-coilcraft-103207315")
      )
      (libsource (lib "Altium Content Vault") (part "725321dda6339637d4d059423bc1c3c"))
    )
    (comp (ref "L6")
      (value "PFL1609-561MEW")
      (footprint "FP-PFL1609-MFG")
      (description "Fixed Inductors PFL1609 Low Profile 0.56 uH 20 % 1.4 A")
      (fields (field (name "MANUFACTURER") "coilcraft") (field (name "TOLERANCE") "20%"))
      (libsource (lib "Altium Content Vault") (part "725321dda6339637d4d059423bc1c3c"))
    )
    (comp (ref "L7")
      (value "ADL32VHC-220M")
      (footprint "FP-1210POC-MFG")
      (description "NOT COILCRAFT - ACTUAL P# --> ADL32VHC-220M\r\n - Power Injection Chokes for PoC")
      (fields
        (field (name "MANUFACTURER") "coilcraft")
        (field (name "OCTOPART") "https://octopart.com/1210poc-223mrc-coilcraft-103207315")
      )
      (libsource (lib "Altium Content Vault") (part "725321dda6339637d4d059423bc1c3c"))
    )
    (comp (ref "L8")
      (value "PFL1609-561MEW")
      (footprint "FP-PFL1609-MFG")
      (description "Fixed Inductors PFL1609 Low Profile 0.56 uH 20 % 1.4 A")
      (fields (field (name "MANUFACTURER") "coilcraft") (field (name "TOLERANCE") "20%"))
      (libsource (lib "Altium Content Vault") (part "725321dda6339637d4d059423bc1c3c"))
    )
    (comp (ref "R25")
      (value "ERJ3EKF2201V")
      (footprint "RESC1608X55X30LL15T15")
      (fields (field (name "MANUFACTURER") "Panasonic"))
      (libsource (lib "Altium Content Vault") (part "RES"))
    )
    (comp (ref "R26")
      (value "ERJ3EKF2201V")
      (footprint "RESC1608X55X30LL15T15")
      (fields (field (name "MANUFACTURER") "Panasonic"))
      (libsource (lib "Altium Content Vault") (part "RES"))
    )
    (comp (ref "R27")
      (value "ERJ-3EKF4020V")
      (footprint "RESC1608X55X30LL15T15")
      (fields (field (name "MANUFACTURER") "Panasonic"))
      (libsource (lib "Altium Content Vault") (part "RES"))
    )
    (comp (ref "R28")
      (value "ERJ3EKF1002V")
      (footprint "RESC1609X55X30LL15T15")
      (description "Chip Resistor, 10 KOhm, +/- 1%, 0.1 W, -55 to 155 degC, 0603 (1608 Metric), RoHS, Tape and Reel")
      (fields (field (name "TOLERANCE") "1%") (field (name "MANUFACTURER") "Panasonic"))
      (libsource (lib "Altium Content Vault") (part "RES-2"))
    )
    (comp (ref "R29")
      (value "ERJ-3EKF49R9V")
      (footprint "RESC1608X55X30ML15T15")
      (fields (field (name "MANUFACTURER") "Panasonic"))
      (libsource (lib "Altium Content Vault") (part "RES"))
    )
    (comp (ref "R30")
      (value "ERJ-3EKF49R9V")
      (footprint "RESC1608X55X30ML15T15")
      (fields (field (name "MANUFACTURER") "Panasonic"))
      (libsource (lib "Altium Content Vault") (part "RES"))
    )
    (comp (ref "R31")
      (value "ERJ-3EKF8062V")
      (footprint "RESC1608X55X30LL15T15")
      (fields (field (name "MANUFACTURER") "Panasonic"))
      (libsource (lib "Altium Content Vault") (part "RES"))
    )
    (comp (ref "R32")
      (value "ERJ-3EKF8062V")
      (footprint "RESC1608X55X30LL15T15")
      (fields (field (name "MANUFACTURER") "Panasonic"))
      (libsource (lib "Altium Content Vault") (part "RES"))
    )
    (comp (ref "R34")
      (value "ERJ-3EKF2052V")
      (footprint "RESC1608X55X30NL15T15")
      (fields (field (name "MANUFACTURER") "Panasonic"))
      (libsource (lib "Altium Content Vault") (part "RES"))
    )
    (comp (ref "R35")
      (value "ERJ-3EKF2052V")
      (footprint "RESC1608X55X30NL15T15")
      (fields (field (name "MANUFACTURER") "Panasonic"))
      (libsource (lib "Altium Content Vault") (part "RES"))
    )
    (comp (ref "R36")
      (value "ERJ-3EKF49R9V")
      (footprint "RESC1608X55X30ML15T15")
      (fields (field (name "MANUFACTURER") "Panasonic"))
      (libsource (lib "Altium Content Vault") (part "RES"))
    )
    (comp (ref "R37")
      (value "ERJ-3EKF49R9V")
      (footprint "RESC1608X55X30ML15T15")
      (fields (field (name "MANUFACTURER") "Panasonic"))
      (libsource (lib "Altium Content Vault") (part "RES"))
    )
    (comp (ref "R38")
      (value "RC0402JR-070RL")
      (footprint "RESC1005X40X25NL05T10")
      (fields (field (name "MANUFACTURER") "Yageo / Phycomp"))
      (libsource (lib "Altium Content Vault") (part "RES"))
    )
    (comp (ref "R39")
      (value "RC0402JR-070RL")
      (footprint "RESC1005X40X25NL05T10")
      (fields (field (name "MANUFACTURER") "Yageo / Phycomp"))
      (libsource (lib "Altium Content Vault") (part "RES"))
    )
    (comp (ref "R40")
      (value "RC0402JR-070RL")
      (footprint "RESC1005X40X25NL05T10")
      (fields (field (name "MANUFACTURER") "Yageo / Phycomp"))
      (libsource (lib "Altium Content Vault") (part "RES"))
    )
    (comp (ref "R41")
      (value "RC0402JR-070RL")
      (footprint "RESC1005X40X25NL05T10")
      (fields (field (name "MANUFACTURER") "Yageo / Phycomp"))
      (libsource (lib "Altium Content Vault") (part "RES"))
    )
    (comp (ref "R42")
      (value "RC0402JR-070RL")
      (footprint "RESC1005X40X25NL05T10")
      (fields (field (name "MANUFACTURER") "Yageo / Phycomp"))
      (libsource (lib "Altium Content Vault") (part "RES"))
    )
    (comp (ref "R43")
      (value "RC0402JR-070RL")
      (footprint "RESC1005X40X25NL05T10")
      (fields (field (name "MANUFACTURER") "Yageo / Phycomp"))
      (libsource (lib "Altium Content Vault") (part "RES"))
    )
    (comp (ref "R44")
      (value "ERJ-3EKF5101V")
      (footprint "FP-ERJ3EK-MFG")
      (description "RES SMD 5.1K OHM 1% 1/10W 0603")
      (fields (field (name "TOLERANCE") "1%"))
      (libsource (lib "Altium Content Vault") (part "1029c3af85768c4190bb7ad29bc67b5"))
    )
    (comp (ref "R45")
      (value "ERJ-3EKF5101V")
      (footprint "FP-ERJ3EK-MFG")
      (description "RES SMD 5.1K OHM 1% 1/10W 0603")
      (fields (field (name "TOLERANCE") "1%"))
      (libsource (lib "Altium Content Vault") (part "1029c3af85768c4190bb7ad29bc67b5"))
    )
    (comp (ref "R46")
      (value "ERJ-3EKF5101V")
      (footprint "FP-ERJ3EK-MFG")
      (description "RES SMD 5.1K OHM 1% 1/10W 0603")
      (fields (field (name "TOLERANCE") "1%"))
      (libsource (lib "Altium Content Vault") (part "1029c3af85768c4190bb7ad29bc67b5"))
    )
    (comp (ref "R47")
      (value "ERJ-3EKF5101V")
      (footprint "FP-ERJ3EK-MFG")
      (description "RES SMD 5.1K OHM 1% 1/10W 0603")
      (fields (field (name "TOLERANCE") "1%"))
      (libsource (lib "Altium Content Vault") (part "1029c3af85768c4190bb7ad29bc67b5"))
    )
    (comp (ref "TP18")
      (value "TPAD6R")
      (footprint "New footprint 1")
      (description "Test Point .6mm")
      (libsource (lib "Space Concordia") (part "TP"))
    )
    (comp (ref "TP19")
      (value "TPAD6R")
      (footprint "New footprint 1")
      (description "Test Point .6mm")
      (libsource (lib "Space Concordia") (part "TP"))
    )
    (comp (ref "TP20")
      (value "TPAD6R")
      (footprint "New footprint 1")
      (description "Test Point .6mm")
      (libsource (lib "Space Concordia") (part "TP"))
    )
    (comp (ref "TP21")
      (value "TPAD6R")
      (footprint "New footprint 1")
      (description "Test Point .6mm")
      (libsource (lib "Space Concordia") (part "TP"))
    )
    (comp (ref "TP22")
      (value "TPAD6R")
      (footprint "New footprint 1")
      (description "Test Point .6mm")
      (libsource (lib "Space Concordia") (part "TP"))
    )
    (comp (ref "TP23")
      (value "TPAD6R")
      (footprint "New footprint 1")
      (description "Test Point .6mm")
      (libsource (lib "Space Concordia") (part "TP"))
    )
    (comp (ref "TP24")
      (value "TPAD6R")
      (footprint "New footprint 1")
      (description "Test Point .6mm")
      (libsource (lib "Space Concordia") (part "TP"))
    )
    (comp (ref "TP25")
      (value "TPAD6R")
      (footprint "New footprint 1")
      (description "Test Point .6mm")
      (libsource (lib "Space Concordia") (part "TP"))
    )
    (comp (ref "TP26")
      (value "TPAD6R")
      (footprint "New footprint 1")
      (description "Test Point .6mm")
      (libsource (lib "Space Concordia") (part "TP"))
    )
    (comp (ref "TP27")
      (value "TPAD6R")
      (footprint "New footprint 1")
      (description "Test Point .6mm")
      (libsource (lib "Space Concordia") (part "TP"))
    )
    (comp (ref "TP28")
      (value "TPAD6R")
      (footprint "New footprint 1")
      (description "Test Point .6mm")
      (libsource (lib "Space Concordia") (part "TP"))
    )
    (comp (ref "TP29")
      (value "TPAD6R")
      (footprint "New footprint 1")
      (description "Test Point .6mm")
      (libsource (lib "Space Concordia") (part "TP"))
    )
    (comp (ref "TP30")
      (value "TPAD6R")
      (footprint "New footprint 1")
      (description "Test Point .6mm")
      (libsource (lib "Space Concordia") (part "TP"))
    )
    (comp (ref "TP31")
      (value "TPAD6R")
      (footprint "New footprint 1")
      (description "Test Point .6mm")
      (libsource (lib "Space Concordia") (part "TP"))
    )
    (comp (ref "TP32")
      (value "TPAD6R")
      (footprint "New footprint 1")
      (description "Test Point .6mm")
      (libsource (lib "Space Concordia") (part "TP"))
    )
    (comp (ref "TP33")
      (value "TPAD6R")
      (footprint "New footprint 1")
      (description "Test Point .6mm")
      (libsource (lib "Space Concordia") (part "TP"))
    )
    (comp (ref "TP34")
      (value "TPAD6R")
      (footprint "New footprint 1")
      (description "Test Point .6mm")
      (libsource (lib "Space Concordia") (part "TP"))
    )
    (comp (ref "TP35")
      (value "TPAD6R")
      (footprint "New footprint 1")
      (description "Test Point .6mm")
      (libsource (lib "Space Concordia") (part "TP"))
    )
    (comp (ref "U1")
      (value "MAX96724FGTN/V+")
      (footprint "MAX96724FGTN_V+-Footprint-1")
      (description "Quad Tunneling GMSL2/1 to CSI-2 Deserializer")
      (libsource (lib "Space Concordia") (part "MAX96724FGTN_V+-Symbol-1"))
    )
    (comp (ref "U2")
      (value "LD1117S18TR")
      (footprint "SOT-223_M")
      (description "Fixed Low Drop Positive Voltage Regulator, 1.8V, 4-Pin SOT-223, Tape and Reel")
      (libsource (lib "Altium Content Vault") (part "PM-REG-LD1117-SOT4"))
    )
    (comp (ref "U3")
      (value "LD1117S12TR")
      (footprint "SOT-223_M")
      (description "Fixed Low Drop Positive Voltage Regulator, 1.2V, 4-Pin SOT-223, Tape and Reel")
      (libsource (lib "Altium Content Vault") (part "PM-REG-LD1117-SOT4"))
    )
    (comp (ref "Y1")
      (value "ABM8G-25.000MHZ-18-D2Y-T")
      (footprint "FP-ABM8G-MFG")
      (description "Crystal 25MHz ±20ppm (Tol) ±30ppm (Stability) 18pF FUND 60Ω 4-Pin SMD T/R")
      (fields (field (name "TOLERANCE") "20ppm"))
      (libsource (lib "Altium Content Vault") (part "48e526d86b7f2615d98721063c72f49"))
    )
  )
  (nets
    (net (code "1") (name "/CAM_1V2") (class "Default")
      (node (ref "C59") (pin "1") (pinfunction "1_1") (pintype "passive"))
      (node (ref "R38") (pin "1") (pinfunction "1_1") (pintype "passive"))
      (node (ref "R39") (pin "1") (pinfunction "1_1") (pintype "passive"))
      (node (ref "R43") (pin "1") (pinfunction "1_1") (pintype "passive"))
      (node (ref "U3") (pin "2") (pinfunction "VOUT_2") (pintype "power_in"))
      (node (ref "U3") (pin "4") (pinfunction "VOUT_4") (pintype "power_in"))
    )
    (net (code "2") (name "/CAM_1V8") (class "Default")
      (node (ref "C45") (pin "1") (pinfunction "1_1") (pintype "passive"))
      (node (ref "R40") (pin "1") (pinfunction "1_1") (pintype "passive"))
      (node (ref "R41") (pin "1") (pinfunction "1_1") (pintype "passive"))
      (node (ref "U2") (pin "2") (pinfunction "VOUT_2") (pintype "power_in"))
      (node (ref "U2") (pin "4") (pinfunction "VOUT_4") (pintype "power_in"))
    )
    (net (code "3") (name "/CAM_I2C_SCL") (class "Default")
      (node (ref "R26") (pin "1") (pinfunction "1_1") (pintype "passive"))
      (node (ref "TP24") (pin "1") (pinfunction "TP_1") (pintype "passive"))
      (node (ref "U1") (pin "29") (pinfunction "SCL_29") (pintype "passive"))
    )
    (net (code "4") (name "/CAM_I2C_SDA") (class "Default")
      (node (ref "R25") (pin "1") (pinfunction "1_1") (pintype "passive"))
      (node (ref "TP22") (pin "1") (pinfunction "TP_1") (pintype "passive"))
      (node (ref "U1") (pin "28") (pinfunction "SDA_28") (pintype "passive"))
    )
    (net (code "5") (name "/CFG0") (class "Default")
      (node (ref "R32") (pin "1") (pinfunction "1_1") (pintype "passive"))
      (node (ref "R35") (pin "2") (pinfunction "2_2") (pintype "passive"))
      (node (ref "TP34") (pin "1") (pinfunction "TP_1") (pintype "passive"))
      (node (ref "U1") (pin "4") (pinfunction "CFG0_4") (pintype "input"))
    )
    (net (code "6") (name "/CKA_N") (class "Default")
      (node (ref "C69") (pin "2") (pinfunction "2_2") (pintype "passive"))
      (node (ref "U1") (pin "40") (pinfunction "CKAN_40") (pintype "bidirectional"))
    )
    (net (code "7") (name "/CKA_P") (class "Default")
      (node (ref "C68") (pin "2") (pinfunction "2_2") (pintype "passive"))
      (node (ref "U1") (pin "39") (pinfunction "CKAP_39") (pintype "bidirectional"))
    )
    (net (code "8") (name "/CKB_N") (class "Default")
      (node (ref "C41") (pin "1") (pinfunction "1_1") (pintype "passive"))
      (node (ref "U1") (pin "46") (pinfunction "NC/CKBN_46") (pintype "passive"))
    )
    (net (code "9") (name "/CKB_P") (class "Default")
      (node (ref "C38") (pin "1") (pinfunction "1_1") (pintype "passive"))
      (node (ref "U1") (pin "45") (pinfunction "NC/CKBP_45") (pintype "passive"))
    )
    (net (code "10") (name "/CKC_N") (class "Default")
      (node (ref "C27") (pin "1") (pinfunction "1_1") (pintype "passive"))
      (node (ref "U1") (pin "34") (pinfunction "CKCN_34") (pintype "bidirectional"))
    )
    (net (code "11") (name "/CKC_P") (class "Default")
      (node (ref "C24") (pin "1") (pinfunction "1_1") (pintype "passive"))
      (node (ref "U1") (pin "33") (pinfunction "CKCP_33") (pintype "bidirectional"))
    )
    (net (code "12") (name "/CKF_N") (class "Default")
      (node (ref "C71") (pin "2") (pinfunction "2_2") (pintype "passive"))
      (node (ref "U1") (pin "52") (pinfunction "NC/CKFN_52") (pintype "passive"))
    )
    (net (code "13") (name "/CKF_P") (class "Default")
      (node (ref "C70") (pin "2") (pinfunction "2_2") (pintype "passive"))
      (node (ref "U1") (pin "51") (pinfunction "NC/CKFP_51") (pintype "passive"))
    )
    (net (code "14") (name "/CSI0_CK_N") (class "Default")
      (node (ref "C27") (pin "2") (pinfunction "2_2") (pintype "passive"))
    )
    (net (code "15") (name "/CSI0_CK_P") (class "Default")
      (node (ref "C24") (pin "2") (pinfunction "2_2") (pintype "passive"))
    )
    (net (code "16") (name "/CSI0_D0_N") (class "Default")
      (node (ref "C15") (pin "2") (pinfunction "2_2") (pintype "passive"))
    )
    (net (code "17") (name "/CSI0_D0_P") (class "Default")
      (node (ref "C14") (pin "2") (pinfunction "2_2") (pintype "passive"))
    )
    (net (code "18") (name "/CSI0_D1_N") (class "Default")
      (node (ref "C17") (pin "2") (pinfunction "2_2") (pintype "passive"))
    )
    (net (code "19") (name "/CSI0_D1_P") (class "Default")
      (node (ref "C16") (pin "2") (pinfunction "2_2") (pintype "passive"))
    )
    (net (code "20") (name "/CSI0_D2_N") (class "Default")
      (node (ref "C19") (pin "2") (pinfunction "2_2") (pintype "passive"))
    )
    (net (code "21") (name "/CSI0_D2_P") (class "Default")
      (node (ref "C18") (pin "2") (pinfunction "2_2") (pintype "passive"))
    )
    (net (code "22") (name "/CSI0_D3_N") (class "Default")
      (node (ref "C23") (pin "2") (pinfunction "2_2") (pintype "passive"))
    )
    (net (code "23") (name "/CSI0_D3_P") (class "Default")
      (node (ref "C22") (pin "2") (pinfunction "2_2") (pintype "passive"))
    )
    (net (code "24") (name "/CSI1_CK_N") (class "Default")
      (node (ref "C41") (pin "2") (pinfunction "2_2") (pintype "passive"))
    )
    (net (code "25") (name "/CSI1_CK_P") (class "Default")
      (node (ref "C38") (pin "2") (pinfunction "2_2") (pintype "passive"))
    )
    (net (code "26") (name "/CSI1_D0_N") (class "Default")
      (node (ref "C29") (pin "2") (pinfunction "2_2") (pintype "passive"))
    )
    (net (code "27") (name "/CSI1_D0_P") (class "Default")
      (node (ref "C28") (pin "2") (pinfunction "2_2") (pintype "passive"))
    )
    (net (code "28") (name "/CSI1_D1_N") (class "Default")
      (node (ref "C31") (pin "2") (pinfunction "2_2") (pintype "passive"))
    )
    (net (code "29") (name "/CSI1_D1_P") (class "Default")
      (node (ref "C30") (pin "2") (pinfunction "2_2") (pintype "passive"))
    )
    (net (code "30") (name "/CSI1_D2_N") (class "Default")
      (node (ref "C33") (pin "2") (pinfunction "2_2") (pintype "passive"))
    )
    (net (code "31") (name "/CSI1_D2_P") (class "Default")
      (node (ref "C32") (pin "2") (pinfunction "2_2") (pintype "passive"))
    )
    (net (code "32") (name "/CSI1_D3_N") (class "Default")
      (node (ref "C37") (pin "2") (pinfunction "2_2") (pintype "passive"))
    )
    (net (code "33") (name "/CSI1_D3_P") (class "Default")
      (node (ref "C36") (pin "2") (pinfunction "2_2") (pintype "passive"))
    )
    (net (code "34") (name "/DA0_N") (class "Default")
      (node (ref "C15") (pin "1") (pinfunction "1_1") (pintype "passive"))
      (node (ref "U1") (pin "32") (pinfunction "DA0N_32") (pintype "bidirectional"))
    )
    (net (code "35") (name "/DA0_P") (class "Default")
      (node (ref "C14") (pin "1") (pinfunction "1_1") (pintype "passive"))
      (node (ref "U1") (pin "31") (pinfunction "DA0P_31") (pintype "bidirectional"))
    )
    (net (code "36") (name "/DA1_N") (class "Default")
      (node (ref "C17") (pin "1") (pinfunction "1_1") (pintype "passive"))
      (node (ref "U1") (pin "36") (pinfunction "DA1N_36") (pintype "bidirectional"))
    )
    (net (code "37") (name "/DA1_P") (class "Default")
      (node (ref "C16") (pin "1") (pinfunction "1_1") (pintype "passive"))
      (node (ref "U1") (pin "35") (pinfunction "DA1P_35") (pintype "bidirectional"))
    )
    (net (code "38") (name "/DA2_N") (class "Default")
      (node (ref "C19") (pin "1") (pinfunction "1_1") (pintype "passive"))
      (node (ref "U1") (pin "38") (pinfunction "DA2N_38") (pintype "bidirectional"))
    )
    (net (code "39") (name "/DA2_P") (class "Default")
      (node (ref "C18") (pin "1") (pinfunction "1_1") (pintype "passive"))
      (node (ref "U1") (pin "37") (pinfunction "DA2P_37") (pintype "bidirectional"))
    )
    (net (code "40") (name "/DA3_N") (class "Default")
      (node (ref "C23") (pin "1") (pinfunction "1_1") (pintype "passive"))
      (node (ref "U1") (pin "42") (pinfunction "DA3N_42") (pintype "bidirectional"))
    )
    (net (code "41") (name "/DA3_P") (class "Default")
      (node (ref "C22") (pin "1") (pinfunction "1_1") (pintype "passive"))
      (node (ref "U1") (pin "41") (pinfunction "DA3P_41") (pintype "bidirectional"))
    )
    (net (code "42") (name "/DB0_N") (class "Default")
      (node (ref "C29") (pin "1") (pinfunction "1_1") (pintype "passive"))
      (node (ref "U1") (pin "44") (pinfunction "NC/DB0N_44") (pintype "passive"))
    )
    (net (code "43") (name "/DB0_P") (class "Default")
      (node (ref "C28") (pin "1") (pinfunction "1_1") (pintype "passive"))
      (node (ref "U1") (pin "43") (pinfunction "NC/DB0P_43") (pintype "passive"))
    )
    (net (code "44") (name "/DB1_N") (class "Default")
      (node (ref "C31") (pin "1") (pinfunction "1_1") (pintype "passive"))
      (node (ref "U1") (pin "48") (pinfunction "NC/DB1N_48") (pintype "passive"))
    )
    (net (code "45") (name "/DB1_P") (class "Default")
      (node (ref "C30") (pin "1") (pinfunction "1_1") (pintype "passive"))
      (node (ref "U1") (pin "47") (pinfunction "NC/DB1P_47") (pintype "passive"))
    )
    (net (code "46") (name "/DB2_N") (class "Default")
      (node (ref "C33") (pin "1") (pinfunction "1_1") (pintype "passive"))
      (node (ref "U1") (pin "50") (pinfunction "NC/DB2N_50") (pintype "passive"))
    )
    (net (code "47") (name "/DB2_P") (class "Default")
      (node (ref "C32") (pin "1") (pinfunction "1_1") (pintype "passive"))
      (node (ref "U1") (pin "49") (pinfunction "NC/DB2P_49") (pintype "passive"))
    )
    (net (code "48") (name "/DB3_N") (class "Default")
      (node (ref "C37") (pin "1") (pinfunction "1_1") (pintype "passive"))
      (node (ref "U1") (pin "54") (pinfunction "NC/DB3N_54") (pintype "passive"))
    )
    (net (code "49") (name "/DB3_P") (class "Default")
      (node (ref "C36") (pin "1") (pinfunction "1_1") (pintype "passive"))
      (node (ref "U1") (pin "53") (pinfunction "NC/DB3P_53") (pintype "passive"))
    )
    (net (code "50") (name "/MFP0") (class "Default")
      (node (ref "TP26") (pin "1") (pinfunction "TP_1") (pintype "passive"))
      (node (ref "U1") (pin "1") (pinfunction "MFP0_1") (pintype "bidirectional"))
    )
    (net (code "51") (name "/MFP1") (class "Default")
      (node (ref "TP28") (pin "1") (pinfunction "TP_1") (pintype "passive"))
      (node (ref "U1") (pin "2") (pinfunction "MFP1_2") (pintype "bidirectional"))
    )
    (net (code "52") (name "/MFP2") (class "Default")
      (node (ref "TP30") (pin "1") (pinfunction "TP_1") (pintype "passive"))
      (node (ref "U1") (pin "3") (pinfunction "MFP2_3") (pintype "bidirectional"))
    )
    (net (code "53") (name "/MFP3") (class "Default")
      (node (ref "TP23") (pin "1") (pinfunction "TP_1") (pintype "passive"))
      (node (ref "U1") (pin "12") (pinfunction "MFP3_12") (pintype "bidirectional"))
    )
    (net (code "54") (name "/MFP4") (class "Default")
      (node (ref "TP25") (pin "1") (pinfunction "TP_1") (pintype "passive"))
      (node (ref "U1") (pin "13") (pinfunction "MFP4_13") (pintype "bidirectional"))
    )
    (net (code "55") (name "/MFP5") (class "Default")
      (node (ref "TP27") (pin "1") (pinfunction "TP_1") (pintype "passive"))
      (node (ref "U1") (pin "14") (pinfunction "MFP5_14") (pintype "bidirectional"))
    )
    (net (code "56") (name "/MFP6") (class "Default")
      (node (ref "R31") (pin "1") (pinfunction "1_1") (pintype "passive"))
      (node (ref "R34") (pin "2") (pinfunction "2_2") (pintype "passive"))
      (node (ref "TP29") (pin "1") (pinfunction "TP_1") (pintype "passive"))
      (node (ref "U1") (pin "25") (pinfunction "CFG1/MFP6_25") (pintype "bidirectional"))
    )
    (net (code "57") (name "/MFP7") (class "Default")
      (node (ref "TP31") (pin "1") (pinfunction "TP_1") (pintype "passive"))
      (node (ref "U1") (pin "26") (pinfunction "SDA1/MFP7_26") (pintype "bidirectional"))
    )
    (net (code "58") (name "/MFP8") (class "Default")
      (node (ref "TP33") (pin "1") (pinfunction "TP_1") (pintype "passive"))
      (node (ref "U1") (pin "27") (pinfunction "SCL1/MFP8_27") (pintype "bidirectional"))
    )
    (net (code "59") (name "/PoC_A") (class "Default")
      (node (ref "C20") (pin "2") (pinfunction "2_2") (pintype "passive"))
      (node (ref "D1") (pin "1") (pinfunction "IO1_1") (pintype "bidirectional"))
      (node (ref "D1") (pin "10") (pinfunction "NC_10") (pintype "passive"))
      (node (ref "J8") (pin "2") (pinfunction "2_2") (pintype "passive"))
      (node (ref "L2") (pin "2") (pinfunction "2_2") (pintype "passive"))
    )
    (net (code "60") (name "/PoC_B") (class "Default")
      (node (ref "C21") (pin "2") (pinfunction "2_2") (pintype "passive"))
      (node (ref "D2") (pin "5") (pinfunction "IO4_5") (pintype "bidirectional"))
      (node (ref "D2") (pin "6") (pinfunction "NC_6") (pintype "passive"))
      (node (ref "J8") (pin "1") (pinfunction "1_1") (pintype "passive"))
      (node (ref "L4") (pin "2") (pinfunction "2_2") (pintype "passive"))
    )
    (net (code "61") (name "/PoC_C") (class "Default")
      (node (ref "C34") (pin "2") (pinfunction "2_2") (pintype "passive"))
      (node (ref "D3") (pin "1") (pinfunction "IO1_1") (pintype "bidirectional"))
      (node (ref "D3") (pin "10") (pinfunction "NC_10") (pintype "passive"))
      (node (ref "J8") (pin "4") (pinfunction "4_4") (pintype "passive"))
      (node (ref "L6") (pin "2") (pinfunction "2_2") (pintype "passive"))
    )
    (net (code "62") (name "/PoC_D") (class "Default")
      (node (ref "C35") (pin "2") (pinfunction "2_2") (pintype "passive"))
      (node (ref "D4") (pin "5") (pinfunction "IO4_5") (pintype "bidirectional"))
      (node (ref "D4") (pin "6") (pinfunction "NC_6") (pintype "passive"))
      (node (ref "J8") (pin "3") (pinfunction "3_3") (pintype "passive"))
      (node (ref "L8") (pin "2") (pinfunction "2_2") (pintype "passive"))
    )
    (net (code "63") (name "/PoC_PWR") (class "Default")
      (node (ref "F2") (pin "1") (pinfunction "1_1") (pintype "passive"))
      (node (ref "F3") (pin "1") (pinfunction "1_1") (pintype "passive"))
      (node (ref "F4") (pin "1") (pinfunction "1_1") (pintype "passive"))
      (node (ref "F5") (pin "1") (pinfunction "1_1") (pintype "passive"))
      (node (ref "TP35") (pin "1") (pinfunction "TP_1") (pintype "passive"))
    )
    (net (code "64") (name "/SIOA_N") (class "Default")
      (node (ref "C25") (pin "1") (pinfunction "1_1") (pintype "passive"))
      (node (ref "U1") (pin "22") (pinfunction "SIOAN_22") (pintype "bidirectional"))
    )
    (net (code "65") (name "/SIOA_P") (class "Default")
      (node (ref "C20") (pin "1") (pinfunction "1_1") (pintype "passive"))
      (node (ref "U1") (pin "23") (pinfunction "SIOAP_23") (pintype "bidirectional"))
    )
    (net (code "66") (name "/SIOB_N") (class "Default")
      (node (ref "C26") (pin "1") (pinfunction "1_1") (pintype "passive"))
      (node (ref "U1") (pin "19") (pinfunction "SIOBN_19") (pintype "bidirectional"))
    )
    (net (code "67") (name "/SIOB_P") (class "Default")
      (node (ref "C21") (pin "1") (pinfunction "1_1") (pintype "passive"))
      (node (ref "U1") (pin "18") (pinfunction "SIOBP_18") (pintype "bidirectional"))
    )
    (net (code "68") (name "/SIOC_N") (class "Default")
      (node (ref "C39") (pin "1") (pinfunction "1_1") (pintype "passive"))
      (node (ref "U1") (pin "9") (pinfunction "SIOCN_9") (pintype "bidirectional"))
    )
    (net (code "69") (name "/SIOC_P") (class "Default")
      (node (ref "C34") (pin "1") (pinfunction "1_1") (pintype "passive"))
      (node (ref "U1") (pin "10") (pinfunction "SIOCP_10") (pintype "bidirectional"))
    )
    (net (code "70") (name "/SIOD_N") (class "Default")
      (node (ref "C40") (pin "1") (pinfunction "1_1") (pintype "passive"))
      (node (ref "U1") (pin "6") (pinfunction "SIODN_6") (pintype "bidirectional"))
    )
    (net (code "71") (name "/SIOD_P") (class "Default")
      (node (ref "C35") (pin "1") (pinfunction "1_1") (pintype "passive"))
      (node (ref "U1") (pin "5") (pinfunction "SIODP_5") (pintype "bidirectional"))
    )
    (net (code "72") (name "/X25_N") (class "Default")
      (node (ref "C43") (pin "2") (pinfunction "2_2") (pintype "passive"))
      (node (ref "U1") (pin "16") (pinfunction "X2_16") (pintype "passive"))
      (node (ref "Y1") (pin "3") (pinfunction "3_3") (pintype "passive"))
    )
    (net (code "73") (name "/X25_P") (class "Default")
      (node (ref "C42") (pin "2") (pinfunction "2_2") (pintype "passive"))
      (node (ref "U1") (pin "15") (pinfunction "X1/OSC_15") (pintype "passive"))
      (node (ref "Y1") (pin "1") (pinfunction "1_1") (pintype "passive"))
    )
    (net (code "74") (name "/XRES") (class "Default")
      (node (ref "R27") (pin "2") (pinfunction "2_2") (pintype "passive"))
      (node (ref "U1") (pin "17") (pinfunction "XRES_17") (pintype "passive"))
    )
    (net (code "75") (name "/nPWDN") (class "Default")
      (node (ref "R28") (pin "1") (pinfunction "1_1") (pintype "passive"))
      (node (ref "TP32") (pin "1") (pinfunction "TP_1") (pintype "passive"))
      (node (ref "U1") (pin "11") (pinfunction "PWDNB_11") (pintype "input"))
    )
    (net (code "76") (name "3V3_AUX") (class "Default")
      (node (ref "R25") (pin "2") (pinfunction "2_2") (pintype "passive"))
      (node (ref "R26") (pin "2") (pinfunction "2_2") (pintype "passive"))
      (node (ref "R28") (pin "2") (pinfunction "2_2") (pintype "passive"))
      (node (ref "R31") (pin "2") (pinfunction "2_2") (pintype "passive"))
      (node (ref "R32") (pin "2") (pinfunction "2_2") (pintype "passive"))
      (node (ref "R42") (pin "1") (pinfunction "1_1") (pintype "passive"))
    )
    (net (code "77") (name "GND") (class "Default")
      (node (ref "C42") (pin "1") (pinfunction "1_1") (pintype "passive"))
      (node (ref "C43") (pin "1") (pinfunction "1_1") (pintype "passive"))
      (node (ref "C44") (pin "1") (pinfunction "1_1") (pintype "passive"))
      (node (ref "C45") (pin "2") (pinfunction "2_2") (pintype "passive"))
      (node (ref "C46") (pin "1") (pinfunction "1_1") (pintype "passive"))
      (node (ref "C47") (pin "1") (pinfunction "1_1") (pintype "passive"))
      (node (ref "C48") (pin "1") (pinfunction "1_1") (pintype "passive"))
      (node (ref "C49") (pin "1") (pinfunction "1_1") (pintype "passive"))
      (node (ref "C50") (pin "1") (pinfunction "1_1") (pintype "passive"))
      (node (ref "C51") (pin "1") (pinfunction "1_1") (pintype "passive"))
      (node (ref "C52") (pin "1") (pinfunction "1_1") (pintype "passive"))
      (node (ref "C53") (pin "1") (pinfunction "1_1") (pintype "passive"))
      (node (ref "C54") (pin "1") (pinfunction "1_1") (pintype "passive"))
      (node (ref "C55") (pin "1") (pinfunction "1_1") (pintype "passive"))
      (node (ref "C56") (pin "1") (pinfunction "1_1") (pintype "passive"))
      (node (ref "C57") (pin "1") (pinfunction "1_1") (pintype "passive"))
      (node (ref "C58") (pin "1") (pinfunction "1_1") (pintype "passive"))
      (node (ref "C59") (pin "2") (pinfunction "2_2") (pintype "passive"))
      (node (ref "C60") (pin "1") (pinfunction "1_1") (pintype "passive"))
      (node (ref "C61") (pin "1") (pinfunction "1_1") (pintype "passive"))
      (node (ref "C62") (pin "1") (pinfunction "1_1") (pintype "passive"))
      (node (ref "C63") (pin "1") (pinfunction "1_1") (pintype "passive"))
      (node (ref "C64") (pin "2") (pinfunction "2_2") (pintype "passive"))
      (node (ref "C65") (pin "2") (pinfunction "2_2") (pintype "passive"))
      (node (ref "C66") (pin "2") (pinfunction "2_2") (pintype "passive"))
      (node (ref "C67") (pin "2") (pinfunction "2_2") (pintype "passive"))
      (node (ref "D1") (pin "3") (pinfunction "GND_3") (pintype "power_in"))
      (node (ref "D1") (pin "8") (pinfunction "GND_8") (pintype "power_in"))
      (node (ref "D2") (pin "3") (pinfunction "GND_3") (pintype "power_in"))
      (node (ref "D2") (pin "8") (pinfunction "GND_8") (pintype "power_in"))
      (node (ref "D3") (pin "3") (pinfunction "GND_3") (pintype "power_in"))
      (node (ref "D3") (pin "8") (pinfunction "GND_8") (pintype "power_in"))
      (node (ref "D4") (pin "3") (pinfunction "GND_3") (pintype "power_in"))
      (node (ref "D4") (pin "8") (pinfunction "GND_8") (pintype "power_in"))
      (node (ref "J8") (pin "MH1") (pinfunction "MH1_MH1") (pintype "passive"))
      (node (ref "J8") (pin "MH2") (pinfunction "MH2_MH2") (pintype "passive"))
      (node (ref "J8") (pin "MH3") (pinfunction "MH3_MH3") (pintype "passive"))
      (node (ref "J8") (pin "MH4") (pinfunction "MH4_MH4") (pintype "passive"))
      (node (ref "J8") (pin "MH5") (pinfunction "MH5_MH5") (pintype "passive"))
      (node (ref "R27") (pin "1") (pinfunction "1_1") (pintype "passive"))
      (node (ref "R29") (pin "1") (pinfunction "1_1") (pintype "passive"))
      (node (ref "R30") (pin "1") (pinfunction "1_1") (pintype "passive"))
      (node (ref "R34") (pin "1") (pinfunction "1_1") (pintype "passive"))
      (node (ref "R35") (pin "1") (pinfunction "1_1") (pintype "passive"))
      (node (ref "R36") (pin "1") (pinfunction "1_1") (pintype "passive"))
      (node (ref "R37") (pin "1") (pinfunction "1_1") (pintype "passive"))
      (node (ref "U1") (pin "57") (pinfunction "GND_(EP)_57") (pintype "power_in"))
      (node (ref "U2") (pin "1") (pinfunction "GND_1") (pintype "power_in"))
      (node (ref "U3") (pin "1") (pinfunction "GND_1") (pintype "power_in"))
      (node (ref "Y1") (pin "2") (pinfunction "GND_2") (pintype "power_in"))
      (node (ref "Y1") (pin "4") (pinfunction "GND_4") (pintype "power_in"))
    )
    (net (code "78") (name "LO_VCC") (class "Default")
      (node (ref "C44") (pin "2") (pinfunction "2_2") (pintype "passive"))
      (node (ref "C58") (pin "2") (pinfunction "2_2") (pintype "passive"))
      (node (ref "U2") (pin "3") (pinfunction "VIN_3") (pintype "power_in"))
      (node (ref "U3") (pin "3") (pinfunction "VIN_3") (pintype "power_in"))
    )
    (net (code "79") (name "Net-(C25-Pad2)") (class "Default")
      (node (ref "C25") (pin "2") (pinfunction "2_2") (pintype "passive"))
      (node (ref "R29") (pin "2") (pinfunction "2_2") (pintype "passive"))
    )
    (net (code "80") (name "Net-(C26-Pad2)") (class "Default")
      (node (ref "C26") (pin "2") (pinfunction "2_2") (pintype "passive"))
      (node (ref "R30") (pin "2") (pinfunction "2_2") (pintype "passive"))
    )
    (net (code "81") (name "Net-(C39-Pad2)") (class "Default")
      (node (ref "C39") (pin "2") (pinfunction "2_2") (pintype "passive"))
      (node (ref "R36") (pin "2") (pinfunction "2_2") (pintype "passive"))
    )
    (net (code "82") (name "Net-(C40-Pad2)") (class "Default")
      (node (ref "C40") (pin "2") (pinfunction "2_2") (pintype "passive"))
      (node (ref "R37") (pin "2") (pinfunction "2_2") (pintype "passive"))
    )
    (net (code "83") (name "Net-(C46-Pad2)") (class "Default")
      (node (ref "C46") (pin "2") (pinfunction "2_2") (pintype "passive"))
      (node (ref "C47") (pin "2") (pinfunction "2_2") (pintype "passive"))
      (node (ref "U1") (pin "8") (pinfunction "CAP_VDD_8") (pintype "power_in"))
    )
    (net (code "84") (name "Net-(C48-Pad2)") (class "Default")
      (node (ref "C48") (pin "2") (pinfunction "2_2") (pintype "passive"))
      (node (ref "C49") (pin "2") (pinfunction "2_2") (pintype "passive"))
      (node (ref "U1") (pin "20") (pinfunction "CAP_VDD_20") (pintype "power_in"))
    )
    (net (code "85") (name "Net-(C50-Pad2)") (class "Default")
      (node (ref "C50") (pin "2") (pinfunction "2_2") (pintype "passive"))
      (node (ref "C51") (pin "2") (pinfunction "2_2") (pintype "passive"))
      (node (ref "R38") (pin "2") (pinfunction "2_2") (pintype "passive"))
      (node (ref "U1") (pin "55") (pinfunction "VDD_55") (pintype "power_in"))
    )
    (net (code "86") (name "Net-(C52-Pad2)") (class "Default")
      (node (ref "C52") (pin "2") (pinfunction "2_2") (pintype "passive"))
      (node (ref "C53") (pin "2") (pinfunction "2_2") (pintype "passive"))
      (node (ref "R39") (pin "2") (pinfunction "2_2") (pintype "passive"))
      (node (ref "U1") (pin "56") (pinfunction "VDD_56") (pintype "power_in"))
    )
    (net (code "87") (name "Net-(C54-Pad2)") (class "Default")
      (node (ref "C54") (pin "2") (pinfunction "2_2") (pintype "passive"))
      (node (ref "C55") (pin "2") (pinfunction "2_2") (pintype "passive"))
      (node (ref "R40") (pin "2") (pinfunction "2_2") (pintype "passive"))
      (node (ref "U1") (pin "7") (pinfunction "VDD18_7") (pintype "power_in"))
    )
    (net (code "88") (name "Net-(C56-Pad2)") (class "Default")
      (node (ref "C56") (pin "2") (pinfunction "2_2") (pintype "passive"))
      (node (ref "C57") (pin "2") (pinfunction "2_2") (pintype "passive"))
      (node (ref "R41") (pin "2") (pinfunction "2_2") (pintype "passive"))
      (node (ref "U1") (pin "21") (pinfunction "VDD18_21") (pintype "power_in"))
    )
    (net (code "89") (name "Net-(C64-Pad1)") (class "Default")
      (node (ref "C64") (pin "1") (pinfunction "1_1") (pintype "passive"))
      (node (ref "F2") (pin "2") (pinfunction "2_2") (pintype "passive"))
      (node (ref "L1") (pin "1") (pinfunction "1_1") (pintype "passive"))
      (node (ref "R44") (pin "1") (pinfunction "1_1") (pintype "passive"))
    )
    (net (code "90") (name "Net-(C65-Pad1)") (class "Default")
      (node (ref "C65") (pin "1") (pinfunction "1_1") (pintype "passive"))
      (node (ref "F3") (pin "2") (pinfunction "2_2") (pintype "passive"))
      (node (ref "L3") (pin "1") (pinfunction "1_1") (pintype "passive"))
      (node (ref "R45") (pin "1") (pinfunction "1_1") (pintype "passive"))
    )
    (net (code "91") (name "Net-(C66-Pad1)") (class "Default")
      (node (ref "C66") (pin "1") (pinfunction "1_1") (pintype "passive"))
      (node (ref "F4") (pin "2") (pinfunction "2_2") (pintype "passive"))
      (node (ref "L5") (pin "1") (pinfunction "1_1") (pintype "passive"))
      (node (ref "R46") (pin "1") (pinfunction "1_1") (pintype "passive"))
    )
    (net (code "92") (name "Net-(C67-Pad1)") (class "Default")
      (node (ref "C67") (pin "1") (pinfunction "1_1") (pintype "passive"))
      (node (ref "F5") (pin "2") (pinfunction "2_2") (pintype "passive"))
      (node (ref "L7") (pin "1") (pinfunction "1_1") (pintype "passive"))
      (node (ref "R47") (pin "1") (pinfunction "1_1") (pintype "passive"))
    )
    (net (code "93") (name "Net-(L1-Pad2)") (class "Default")
      (node (ref "L1") (pin "2") (pinfunction "2_2") (pintype "passive"))
      (node (ref "L2") (pin "1") (pinfunction "1_1") (pintype "passive"))
      (node (ref "R44") (pin "2") (pinfunction "2_2") (pintype "passive"))
    )
    (net (code "94") (name "Net-(L3-Pad2)") (class "Default")
      (node (ref "L3") (pin "2") (pinfunction "2_2") (pintype "passive"))
      (node (ref "L4") (pin "1") (pinfunction "1_1") (pintype "passive"))
      (node (ref "R45") (pin "2") (pinfunction "2_2") (pintype "passive"))
    )
    (net (code "95") (name "Net-(L5-Pad2)") (class "Default")
      (node (ref "L5") (pin "2") (pinfunction "2_2") (pintype "passive"))
      (node (ref "L6") (pin "1") (pinfunction "1_1") (pintype "passive"))
      (node (ref "R46") (pin "2") (pinfunction "2_2") (pintype "passive"))
    )
    (net (code "96") (name "Net-(L7-Pad2)") (class "Default")
      (node (ref "L7") (pin "2") (pinfunction "2_2") (pintype "passive"))
      (node (ref "L8") (pin "1") (pinfunction "1_1") (pintype "passive"))
      (node (ref "R47") (pin "2") (pinfunction "2_2") (pintype "passive"))
    )
    (net (code "97") (name "Net-(TP18-TP)") (class "Default")
      (node (ref "C68") (pin "1") (pinfunction "1_1") (pintype "passive"))
      (node (ref "TP18") (pin "1") (pinfunction "TP_1") (pintype "passive"))
    )
    (net (code "98") (name "Net-(TP19-TP)") (class "Default")
      (node (ref "C69") (pin "1") (pinfunction "1_1") (pintype "passive"))
      (node (ref "TP19") (pin "1") (pinfunction "TP_1") (pintype "passive"))
    )
    (net (code "99") (name "Net-(TP20-TP)") (class "Default")
      (node (ref "C70") (pin "1") (pinfunction "1_1") (pintype "passive"))
      (node (ref "TP20") (pin "1") (pinfunction "TP_1") (pintype "passive"))
    )
    (net (code "100") (name "Net-(TP21-TP)") (class "Default")
      (node (ref "C71") (pin "1") (pinfunction "1_1") (pintype "passive"))
      (node (ref "TP21") (pin "1") (pinfunction "TP_1") (pintype "passive"))
    )
    (net (code "101") (name "Net-(U1B-VDDIO)") (class "Default")
      (node (ref "C60") (pin "2") (pinfunction "2_2") (pintype "passive"))
      (node (ref "C61") (pin "2") (pinfunction "2_2") (pintype "passive"))
      (node (ref "R42") (pin "2") (pinfunction "2_2") (pintype "passive"))
      (node (ref "U1") (pin "24") (pinfunction "VDDIO_24") (pintype "power_in"))
    )
    (net (code "102") (name "Net-(U1B-VTERM)") (class "Default")
      (node (ref "C62") (pin "2") (pinfunction "2_2") (pintype "passive"))
      (node (ref "C63") (pin "2") (pinfunction "2_2") (pintype "passive"))
      (node (ref "R43") (pin "2") (pinfunction "2_2") (pintype "passive"))
      (node (ref "U1") (pin "30") (pinfunction "VTERM_30") (pintype "power_in"))
    )
    (net (code "103") (name "unconnected-(D1-IO2-Pad2)") (class "Default")
      (node (ref "D1") (pin "2") (pinfunction "IO2_2") (pintype "bidirectional"))
    )
    (net (code "104") (name "unconnected-(D1-IO3-Pad4)") (class "Default")
      (node (ref "D1") (pin "4") (pinfunction "IO3_4") (pintype "bidirectional"))
    )
    (net (code "105") (name "unconnected-(D1-IO4-Pad5)") (class "Default")
      (node (ref "D1") (pin "5") (pinfunction "IO4_5") (pintype "bidirectional"))
    )
    (net (code "106") (name "unconnected-(D1-NC-Pad6)") (class "Default")
      (node (ref "D1") (pin "6") (pinfunction "NC_6") (pintype "passive"))
    )
    (net (code "107") (name "unconnected-(D1-NC-Pad7)") (class "Default")
      (node (ref "D1") (pin "7") (pinfunction "NC_7") (pintype "passive"))
    )
    (net (code "108") (name "unconnected-(D1-NC-Pad9)") (class "Default")
      (node (ref "D1") (pin "9") (pinfunction "NC_9") (pintype "passive"))
    )
    (net (code "109") (name "unconnected-(D2-IO1-Pad1)") (class "Default")
      (node (ref "D2") (pin "1") (pinfunction "IO1_1") (pintype "bidirectional"))
    )
    (net (code "110") (name "unconnected-(D2-IO2-Pad2)") (class "Default")
      (node (ref "D2") (pin "2") (pinfunction "IO2_2") (pintype "bidirectional"))
    )
    (net (code "111") (name "unconnected-(D2-IO3-Pad4)") (class "Default")
      (node (ref "D2") (pin "4") (pinfunction "IO3_4") (pintype "bidirectional"))
    )
    (net (code "112") (name "unconnected-(D2-NC-Pad7)") (class "Default")
      (node (ref "D2") (pin "7") (pinfunction "NC_7") (pintype "passive"))
    )
    (net (code "113") (name "unconnected-(D2-NC-Pad9)") (class "Default")
      (node (ref "D2") (pin "9") (pinfunction "NC_9") (pintype "passive"))
    )
    (net (code "114") (name "unconnected-(D2-NC-Pad10)") (class "Default")
      (node (ref "D2") (pin "10") (pinfunction "NC_10") (pintype "passive"))
    )
    (net (code "115") (name "unconnected-(D3-IO2-Pad2)") (class "Default")
      (node (ref "D3") (pin "2") (pinfunction "IO2_2") (pintype "bidirectional"))
    )
    (net (code "116") (name "unconnected-(D3-IO3-Pad4)") (class "Default")
      (node (ref "D3") (pin "4") (pinfunction "IO3_4") (pintype "bidirectional"))
    )
    (net (code "117") (name "unconnected-(D3-IO4-Pad5)") (class "Default")
      (node (ref "D3") (pin "5") (pinfunction "IO4_5") (pintype "bidirectional"))
    )
    (net (code "118") (name "unconnected-(D3-NC-Pad6)") (class "Default")
      (node (ref "D3") (pin "6") (pinfunction "NC_6") (pintype "passive"))
    )
    (net (code "119") (name "unconnected-(D3-NC-Pad7)") (class "Default")
      (node (ref "D3") (pin "7") (pinfunction "NC_7") (pintype "passive"))
    )
    (net (code "120") (name "unconnected-(D3-NC-Pad9)") (class "Default")
      (node (ref "D3") (pin "9") (pinfunction "NC_9") (pintype "passive"))
    )
    (net (code "121") (name "unconnected-(D4-IO1-Pad1)") (class "Default")
      (node (ref "D4") (pin "1") (pinfunction "IO1_1") (pintype "bidirectional"))
    )
    (net (code "122") (name "unconnected-(D4-IO2-Pad2)") (class "Default")
      (node (ref "D4") (pin "2") (pinfunction "IO2_2") (pintype "bidirectional"))
    )
    (net (code "123") (name "unconnected-(D4-IO3-Pad4)") (class "Default")
      (node (ref "D4") (pin "4") (pinfunction "IO3_4") (pintype "bidirectional"))
    )
    (net (code "124") (name "unconnected-(D4-NC-Pad7)") (class "Default")
      (node (ref "D4") (pin "7") (pinfunction "NC_7") (pintype "passive"))
    )
    (net (code "125") (name "unconnected-(D4-NC-Pad9)") (class "Default")
      (node (ref "D4") (pin "9") (pinfunction "NC_9") (pintype "passive"))
    )
    (net (code "126") (name "unconnected-(D4-NC-Pad10)") (class "Default")
      (node (ref "D4") (pin "10") (pinfunction "NC_10") (pintype "passive"))
    )
  )
)
